# HLK-7621-ALL-KIT-V1_0.net
KiCad netlist of a schematic drawn in Altium Designer
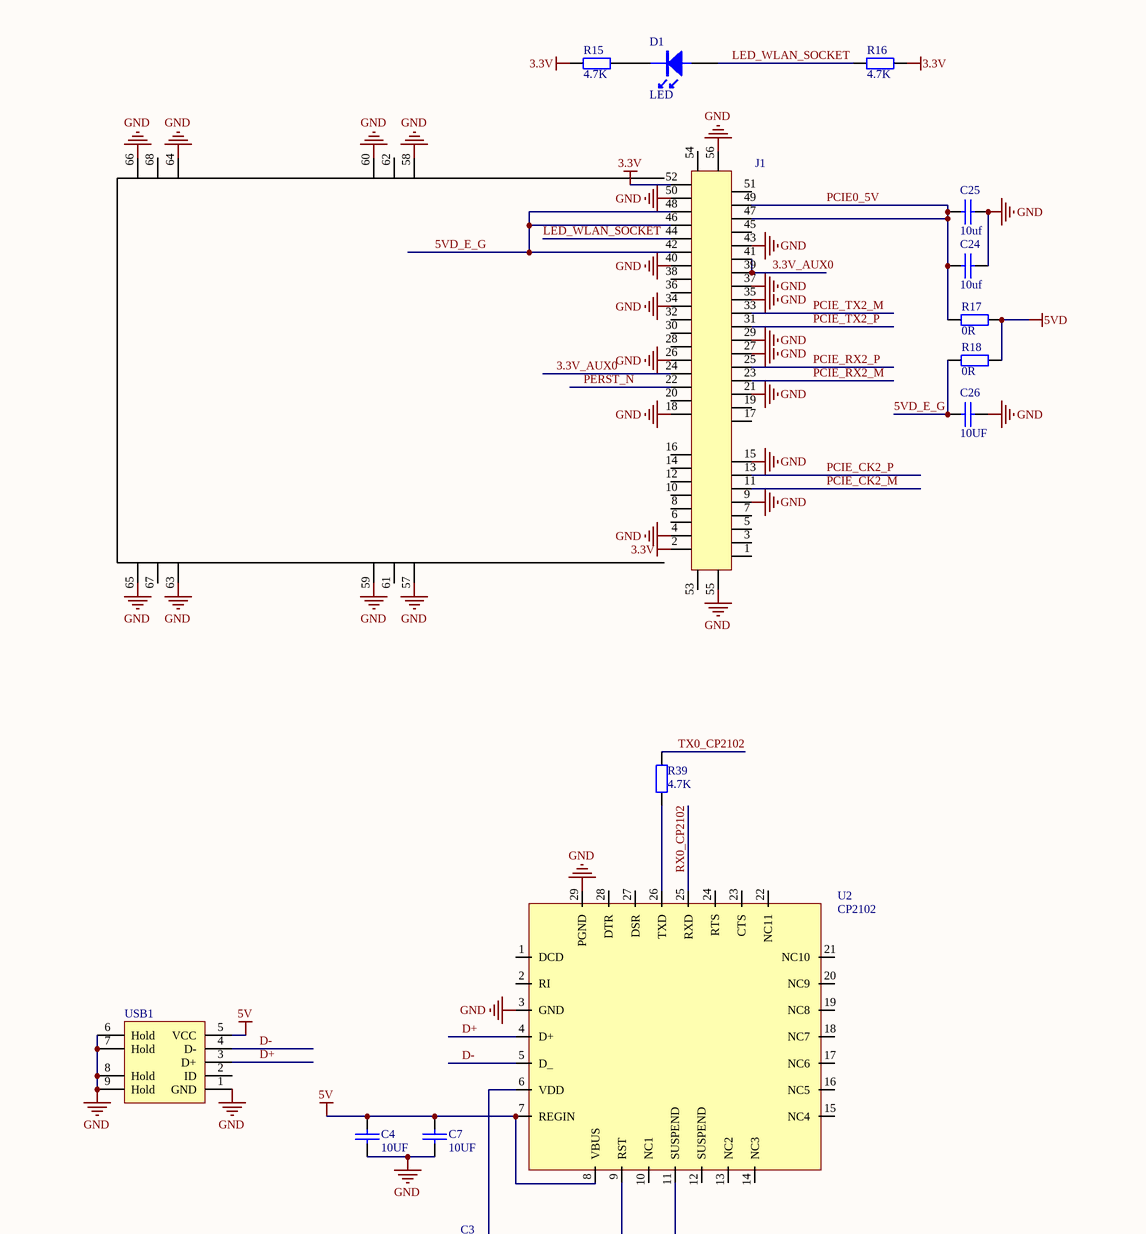
[diagram p0: HLK-7621-ALL-KIT-V1.0.SchDoc, top left]
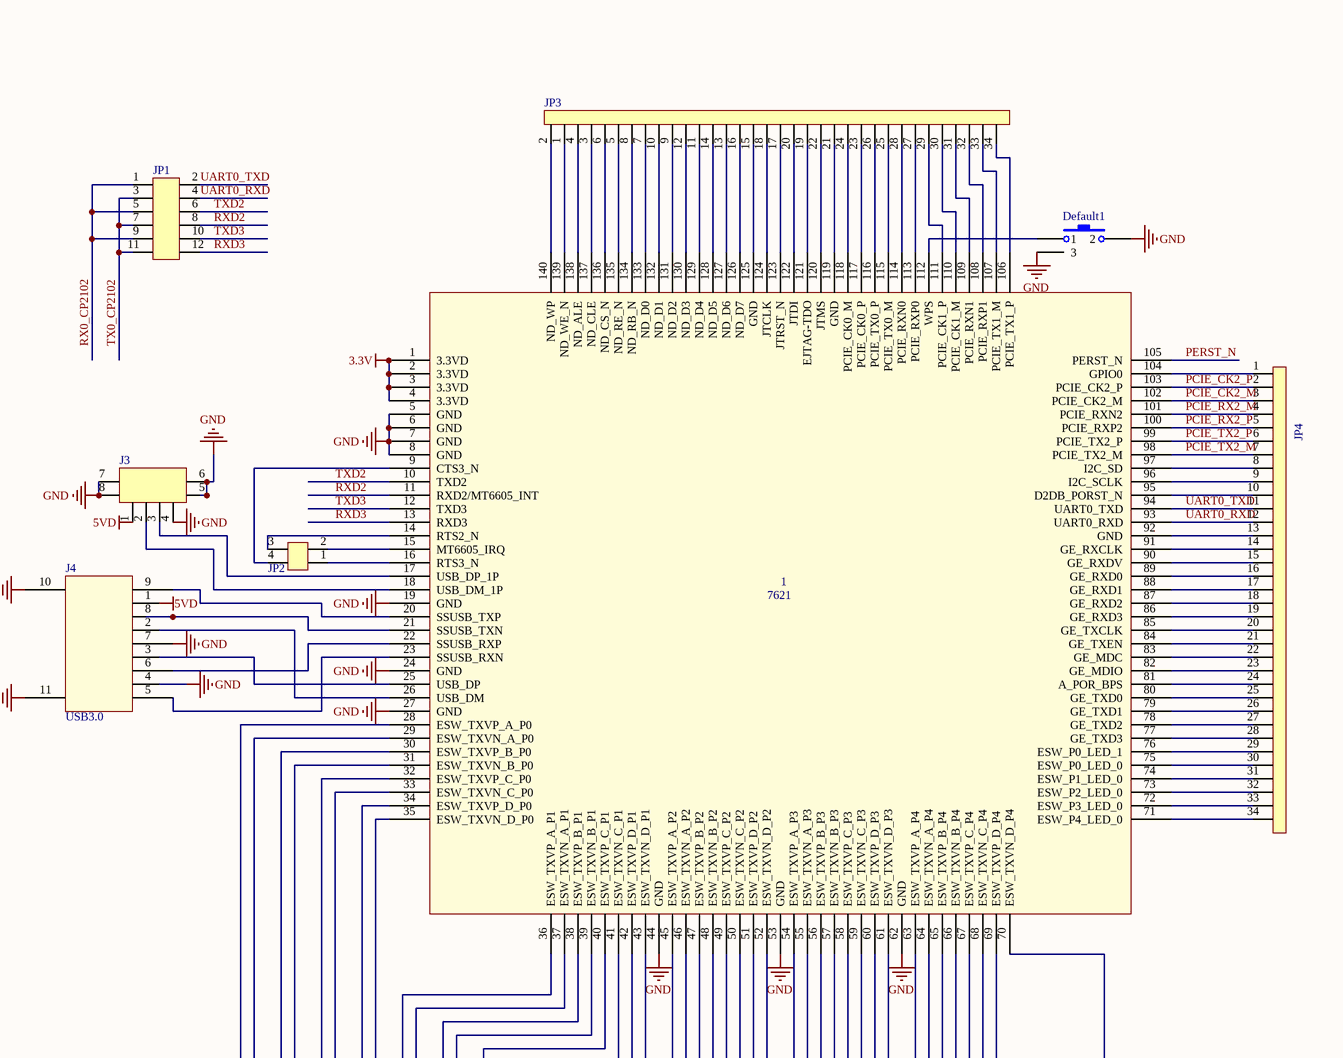
[diagram p1: HLK-7621-ALL-KIT-V1.0.SchDoc, top right]
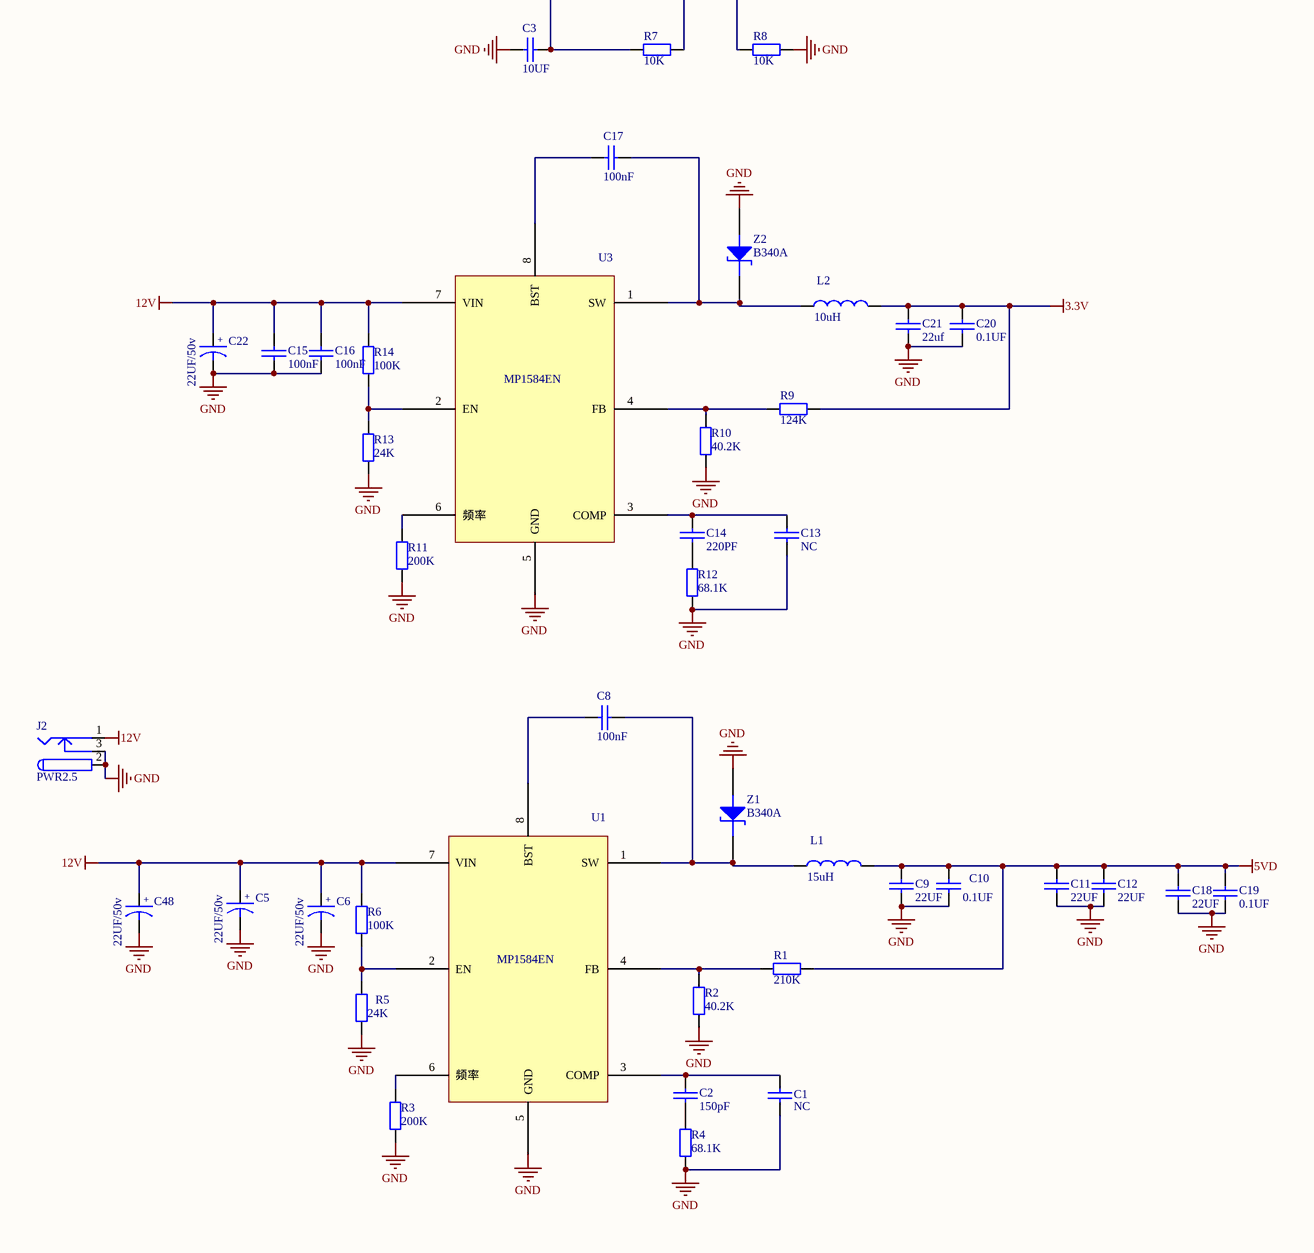
[diagram p2: HLK-7621-ALL-KIT-V1.0.SchDoc, bottom left]
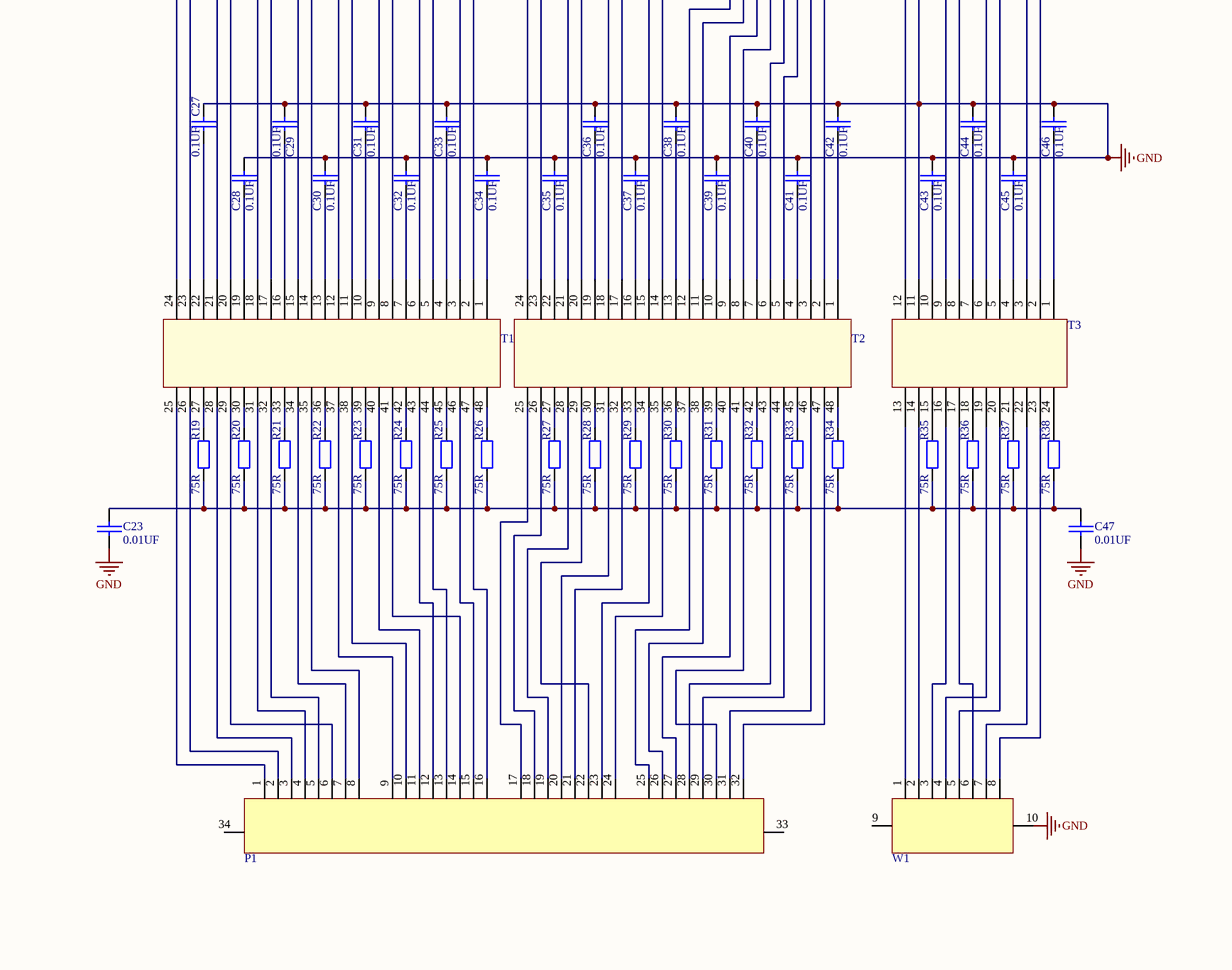
[diagram p3: HLK-7621-ALL-KIT-V1.0.SchDoc, bottom right]

(export (version "E")
  (design (tool "Eeschema 10.0.6"))
  (components
    (comp (ref "1") (value "7621") (footprint "HLK-7621") (libsource (lib "Schlib1") (part "7621")))
    (comp (ref "C1")
      (value "NC")
      (footprint "0603")
      (description "Capacitor")
      (libsource (lib "*") (part "CAP"))
    )
    (comp (ref "C2")
      (value "150pF")
      (footprint "0603")
      (description "Capacitor")
      (libsource (lib "*") (part "CAP"))
    )
    (comp (ref "C3")
      (value "10UF")
      (footprint "0603L")
      (description "Capacitor")
      (libsource (lib "*") (part "CAP"))
    )
    (comp (ref "C4")
      (value "10UF")
      (footprint "0603L")
      (description "Capacitor")
      (libsource (lib "*") (part "CAP"))
    )
    (comp (ref "C5")
      (value "22UF/50v")
      (footprint "0603")
      (description "Capacitor")
      (libsource (lib "Miscellaneous Devices") (part "CAPACITOR POL"))
    )
    (comp (ref "C6")
      (value "22UF/50v")
      (footprint "0603")
      (description "Capacitor")
      (libsource (lib "Miscellaneous Devices") (part "CAPACITOR POL"))
    )
    (comp (ref "C7")
      (value "10UF")
      (footprint "0603L")
      (description "Capacitor")
      (libsource (lib "*") (part "CAP"))
    )
    (comp (ref "C8")
      (value "100nF")
      (footprint "0603")
      (description "Capacitor")
      (libsource (lib "*") (part "CAP"))
    )
    (comp (ref "C9")
      (value "22UF")
      (footprint "0603")
      (description "Capacitor")
      (libsource (lib "*") (part "CAP"))
    )
    (comp (ref "C10")
      (value "0.1UF")
      (footprint "0603")
      (description "Capacitor")
      (libsource (lib "*") (part "CAP"))
    )
    (comp (ref "C11")
      (value "22UF")
      (footprint "0603")
      (description "Capacitor")
      (libsource (lib "*") (part "CAP"))
    )
    (comp (ref "C12")
      (value "22UF")
      (footprint "0603")
      (description "Capacitor")
      (libsource (lib "*") (part "CAP"))
    )
    (comp (ref "C13")
      (value "NC")
      (footprint "0603")
      (description "Capacitor")
      (libsource (lib "*") (part "CAP"))
    )
    (comp (ref "C14")
      (value "220PF")
      (footprint "0603")
      (description "Capacitor")
      (libsource (lib "*") (part "CAP"))
    )
    (comp (ref "C15")
      (value "100nF")
      (footprint "0603")
      (description "Capacitor")
      (libsource (lib "*") (part "CAP"))
    )
    (comp (ref "C16")
      (value "100nF")
      (footprint "0603")
      (description "Capacitor")
      (libsource (lib "*") (part "CAP"))
    )
    (comp (ref "C17")
      (value "100nF")
      (footprint "0603")
      (description "Capacitor")
      (libsource (lib "*") (part "CAP"))
    )
    (comp (ref "C18")
      (value "22UF")
      (footprint "0603")
      (description "Capacitor")
      (libsource (lib "*") (part "CAP"))
    )
    (comp (ref "C19")
      (value "0.1UF")
      (footprint "0603")
      (description "Capacitor")
      (libsource (lib "*") (part "CAP"))
    )
    (comp (ref "C20")
      (value "0.1UF")
      (footprint "0603")
      (description "Capacitor")
      (libsource (lib "*") (part "CAP"))
    )
    (comp (ref "C21")
      (value "22uf")
      (footprint "0603")
      (description "Capacitor")
      (libsource (lib "*") (part "CAP"))
    )
    (comp (ref "C22")
      (value "22UF/50v")
      (footprint "CAP_SMT_8*10.5")
      (description "Capacitor")
      (libsource (lib "Miscellaneous Devices") (part "CAPACITOR POL"))
    )
    (comp (ref "C23")
      (value "0.01UF")
      (footprint "C1206")
      (description "Capacitor")
      (libsource (lib "*") (part "CAP"))
    )
    (comp (ref "C24")
      (value "10uf")
      (footprint "C1206")
      (description "Capacitor")
      (libsource (lib "*") (part "CAP"))
    )
    (comp (ref "C25")
      (value "10uf")
      (footprint "C1206")
      (description "Capacitor")
      (libsource (lib "*") (part "CAP"))
    )
    (comp (ref "C26")
      (value "10UF")
      (footprint "C1206")
      (description "Capacitor")
      (libsource (lib "*") (part "CAP"))
    )
    (comp (ref "C27")
      (value "0.1UF")
      (footprint "C0402")
      (description "Capacitor")
      (libsource (lib "*") (part "CAP"))
    )
    (comp (ref "C28")
      (value "0.1UF")
      (footprint "C0402")
      (description "Capacitor")
      (libsource (lib "*") (part "CAP"))
    )
    (comp (ref "C29")
      (value "0.1UF")
      (footprint "C0402")
      (description "Capacitor")
      (libsource (lib "*") (part "CAP"))
    )
    (comp (ref "C30")
      (value "0.1UF")
      (footprint "C0402")
      (description "Capacitor")
      (libsource (lib "*") (part "CAP"))
    )
    (comp (ref "C31")
      (value "0.1UF")
      (footprint "C0402")
      (description "Capacitor")
      (libsource (lib "*") (part "CAP"))
    )
    (comp (ref "C32")
      (value "0.1UF")
      (footprint "C0402")
      (description "Capacitor")
      (libsource (lib "*") (part "CAP"))
    )
    (comp (ref "C33")
      (value "0.1UF")
      (footprint "C0402")
      (description "Capacitor")
      (libsource (lib "*") (part "CAP"))
    )
    (comp (ref "C34")
      (value "0.1UF")
      (footprint "C0402")
      (description "Capacitor")
      (libsource (lib "*") (part "CAP"))
    )
    (comp (ref "C35")
      (value "0.1UF")
      (footprint "C0402")
      (description "Capacitor")
      (libsource (lib "*") (part "CAP"))
    )
    (comp (ref "C36")
      (value "0.1UF")
      (footprint "C0402")
      (description "Capacitor")
      (libsource (lib "*") (part "CAP"))
    )
    (comp (ref "C37")
      (value "0.1UF")
      (footprint "C0402")
      (description "Capacitor")
      (libsource (lib "*") (part "CAP"))
    )
    (comp (ref "C38")
      (value "0.1UF")
      (footprint "C0402")
      (description "Capacitor")
      (libsource (lib "*") (part "CAP"))
    )
    (comp (ref "C39")
      (value "0.1UF")
      (footprint "C0402")
      (description "Capacitor")
      (libsource (lib "*") (part "CAP"))
    )
    (comp (ref "C40")
      (value "0.1UF")
      (footprint "C0402")
      (description "Capacitor")
      (libsource (lib "*") (part "CAP"))
    )
    (comp (ref "C41")
      (value "0.1UF")
      (footprint "C0402")
      (description "Capacitor")
      (libsource (lib "*") (part "CAP"))
    )
    (comp (ref "C42")
      (value "0.1UF")
      (footprint "C0402")
      (description "Capacitor")
      (libsource (lib "*") (part "CAP"))
    )
    (comp (ref "C43")
      (value "0.1UF")
      (footprint "C0402")
      (description "Capacitor")
      (libsource (lib "*") (part "CAP"))
    )
    (comp (ref "C44")
      (value "0.1UF")
      (footprint "C0402")
      (description "Capacitor")
      (libsource (lib "*") (part "CAP"))
    )
    (comp (ref "C45")
      (value "0.1UF")
      (footprint "C0402")
      (description "Capacitor")
      (libsource (lib "*") (part "CAP"))
    )
    (comp (ref "C46")
      (value "0.1UF")
      (footprint "C0402")
      (description "Capacitor")
      (libsource (lib "*") (part "CAP"))
    )
    (comp (ref "C47")
      (value "0.01UF")
      (footprint "C1206")
      (description "Capacitor")
      (libsource (lib "*") (part "CAP"))
    )
    (comp (ref "C48")
      (value "22UF/50v")
      (footprint "CAP_SMT_8*10.5")
      (description "Capacitor")
      (libsource (lib "Miscellaneous Devices") (part "CAPACITOR POL"))
    )
    (comp (ref "D1") (value "LED") (footprint "C1206") (libsource (lib "*") (part "LED")))
    (comp (ref "Default1")
      (value "SW-PB")
      (footprint "K5")
      (description "Switch")
      (fields (field (name "PUBLISHER") "Altium Limited"))
      (libsource (lib "Miscellaneous Devices") (part "SW-PB"))
    )
    (comp (ref "J1")
      (value "~")
      (footprint "CONSG/54/MINICARD/AS0B22-S68-7F/HALF/FUL")
      (libsource (lib "Schlib1") (part "Component_1"))
    )
    (comp (ref "J2")
      (value "PWR2.5")
      (description "Low Voltage Power Supply Connector")
      (fields (field (name "PUBLISHER") "Altium Limited"))
      (libsource (lib "*") (part "PWR2.5"))
    )
    (comp (ref "J3") (value "~") (libsource (lib "") (part "2_2")))
    (comp (ref "J4") (value "USB3.0") (libsource (lib "Schlib1") (part "USB3.0/9P/DIP/MAINSUPER")))
    (comp (ref "JP1") (value "~") (footprint "HDR2X6") (libsource (lib "") (part "Component_1_3")))
    (comp (ref "JP2") (value "~") (footprint "HDR2X2") (libsource (lib "") (part "2_1")))
    (comp (ref "JP3") (value "~") (footprint "HDR2X17") (libsource (lib "Schlib1") (part "2")))
    (comp (ref "JP4") (value "2") (footprint "HDR2X17") (libsource (lib "") (part "2_3")))
    (comp (ref "L1") (value "15uH") (footprint "CD105") (libsource (lib "startkit") (part "INDUCTOR1")))
    (comp (ref "L2") (value "10uH") (footprint "CD105") (libsource (lib "startkit") (part "INDUCTOR1")))
    (comp (ref "P1")
      (value "Component_2")
      (footprint "PHJ8X4_N")
      (libsource (lib "Schlib1") (part "Component_2"))
    )
    (comp (ref "R1")
      (value "210K")
      (footprint "0603")
      (description "Resistor")
      (fields (field (name "PUBLISHER") "Altium Limited"))
      (libsource (lib "") (part "Res2_1"))
    )
    (comp (ref "R2")
      (value "40.2K")
      (footprint "0603")
      (description "Resistor")
      (fields (field (name "PUBLISHER") "Altium Limited"))
      (libsource (lib "Miscellaneous Devices") (part "Res2"))
    )
    (comp (ref "R3")
      (value "200K")
      (footprint "0603")
      (description "Resistor")
      (fields (field (name "PUBLISHER") "Altium Limited"))
      (libsource (lib "Miscellaneous Devices") (part "Res2"))
    )
    (comp (ref "R4")
      (value "68.1K")
      (footprint "0603")
      (description "Resistor")
      (fields (field (name "PUBLISHER") "Altium Limited"))
      (libsource (lib "Miscellaneous Devices") (part "Res2"))
    )
    (comp (ref "R5")
      (value "24K")
      (footprint "0603")
      (description "Resistor")
      (fields (field (name "PUBLISHER") "Altium Limited"))
      (libsource (lib "Miscellaneous Devices") (part "Res2"))
    )
    (comp (ref "R6")
      (value "100K")
      (footprint "0603")
      (description "Resistor")
      (fields (field (name "PUBLISHER") "Altium Limited"))
      (libsource (lib "Miscellaneous Devices") (part "Res2"))
    )
    (comp (ref "R7")
      (value "10K")
      (footprint "0603L")
      (description "Resistor")
      (fields (field (name "PUBLISHER") "Altium Limited"))
      (libsource (lib "") (part "Res2_3"))
    )
    (comp (ref "R8")
      (value "10K")
      (footprint "0603L")
      (description "Resistor")
      (fields (field (name "PUBLISHER") "Altium Limited"))
      (libsource (lib "") (part "Res2_1"))
    )
    (comp (ref "R9")
      (value "124K")
      (footprint "0603")
      (description "Resistor")
      (fields (field (name "PUBLISHER") "Altium Limited"))
      (libsource (lib "") (part "Res2_1"))
    )
    (comp (ref "R10")
      (value "40.2K")
      (footprint "0603")
      (description "Resistor")
      (fields (field (name "PUBLISHER") "Altium Limited"))
      (libsource (lib "Miscellaneous Devices") (part "Res2"))
    )
    (comp (ref "R11")
      (value "200K")
      (footprint "0603")
      (description "Resistor")
      (fields (field (name "PUBLISHER") "Altium Limited"))
      (libsource (lib "Miscellaneous Devices") (part "Res2"))
    )
    (comp (ref "R12")
      (value "68.1K")
      (footprint "0603")
      (description "Resistor")
      (fields (field (name "PUBLISHER") "Altium Limited"))
      (libsource (lib "Miscellaneous Devices") (part "Res2"))
    )
    (comp (ref "R13")
      (value "24K")
      (footprint "0603")
      (description "Resistor")
      (fields (field (name "PUBLISHER") "Altium Limited"))
      (libsource (lib "Miscellaneous Devices") (part "Res2"))
    )
    (comp (ref "R14")
      (value "100K")
      (footprint "0603")
      (description "Resistor")
      (fields (field (name "PUBLISHER") "Altium Limited"))
      (libsource (lib "Miscellaneous Devices") (part "Res2"))
    )
    (comp (ref "R15")
      (value "4.7K")
      (footprint "0603")
      (description "Resistor")
      (fields (field (name "PUBLISHER") "Altium Limited"))
      (libsource (lib "") (part "Res2_1"))
    )
    (comp (ref "R16")
      (value "4.7K")
      (footprint "0603")
      (description "Resistor")
      (fields (field (name "PUBLISHER") "Altium Limited"))
      (libsource (lib "") (part "Res2_1"))
    )
    (comp (ref "R17")
      (value "0R")
      (footprint "L0805")
      (description "Resistor")
      (fields (field (name "PUBLISHER") "Altium Limited"))
      (libsource (lib "") (part "Res2_3"))
    )
    (comp (ref "R18")
      (value "0R")
      (footprint "R1206")
      (description "Resistor")
      (fields (field (name "PUBLISHER") "Altium Limited"))
      (libsource (lib "") (part "Res2_1"))
    )
    (comp (ref "R19")
      (value "75R")
      (footprint "R0402")
      (description "Resistor")
      (fields (field (name "PUBLISHER") "Altium Limited"))
      (libsource (lib "Schlib1") (part "Res2"))
    )
    (comp (ref "R20")
      (value "75R")
      (footprint "R0402")
      (description "Resistor")
      (fields (field (name "PUBLISHER") "Altium Limited"))
      (libsource (lib "Schlib1") (part "Res2"))
    )
    (comp (ref "R21")
      (value "75R")
      (footprint "R0402")
      (description "Resistor")
      (fields (field (name "PUBLISHER") "Altium Limited"))
      (libsource (lib "Schlib1") (part "Res2"))
    )
    (comp (ref "R22")
      (value "75R")
      (footprint "R0402")
      (description "Resistor")
      (fields (field (name "PUBLISHER") "Altium Limited"))
      (libsource (lib "Schlib1") (part "Res2"))
    )
    (comp (ref "R23")
      (value "75R")
      (footprint "R0402")
      (description "Resistor")
      (fields (field (name "PUBLISHER") "Altium Limited"))
      (libsource (lib "Schlib1") (part "Res2"))
    )
    (comp (ref "R24")
      (value "75R")
      (footprint "R0402")
      (description "Resistor")
      (fields (field (name "PUBLISHER") "Altium Limited"))
      (libsource (lib "Schlib1") (part "Res2"))
    )
    (comp (ref "R25")
      (value "75R")
      (footprint "R0402")
      (description "Resistor")
      (fields (field (name "PUBLISHER") "Altium Limited"))
      (libsource (lib "Schlib1") (part "Res2"))
    )
    (comp (ref "R26")
      (value "75R")
      (footprint "R0402")
      (description "Resistor")
      (fields (field (name "PUBLISHER") "Altium Limited"))
      (libsource (lib "Schlib1") (part "Res2"))
    )
    (comp (ref "R27")
      (value "75R")
      (footprint "R0402")
      (description "Resistor")
      (fields (field (name "PUBLISHER") "Altium Limited"))
      (libsource (lib "Schlib1") (part "Res2"))
    )
    (comp (ref "R28")
      (value "75R")
      (footprint "R0402")
      (description "Resistor")
      (fields (field (name "PUBLISHER") "Altium Limited"))
      (libsource (lib "Schlib1") (part "Res2"))
    )
    (comp (ref "R29")
      (value "75R")
      (footprint "R0402")
      (description "Resistor")
      (fields (field (name "PUBLISHER") "Altium Limited"))
      (libsource (lib "Schlib1") (part "Res2"))
    )
    (comp (ref "R30")
      (value "75R")
      (footprint "R0402")
      (description "Resistor")
      (fields (field (name "PUBLISHER") "Altium Limited"))
      (libsource (lib "Schlib1") (part "Res2"))
    )
    (comp (ref "R31")
      (value "75R")
      (footprint "R0402")
      (description "Resistor")
      (fields (field (name "PUBLISHER") "Altium Limited"))
      (libsource (lib "Schlib1") (part "Res2"))
    )
    (comp (ref "R32")
      (value "75R")
      (footprint "R0402")
      (description "Resistor")
      (fields (field (name "PUBLISHER") "Altium Limited"))
      (libsource (lib "Schlib1") (part "Res2"))
    )
    (comp (ref "R33")
      (value "75R")
      (footprint "R0402")
      (description "Resistor")
      (fields (field (name "PUBLISHER") "Altium Limited"))
      (libsource (lib "Schlib1") (part "Res2"))
    )
    (comp (ref "R34")
      (value "75R")
      (footprint "R0402")
      (description "Resistor")
      (fields (field (name "PUBLISHER") "Altium Limited"))
      (libsource (lib "Schlib1") (part "Res2"))
    )
    (comp (ref "R35")
      (value "75R")
      (footprint "R0402")
      (description "Resistor")
      (fields (field (name "PUBLISHER") "Altium Limited"))
      (libsource (lib "Schlib1") (part "Res2"))
    )
    (comp (ref "R36")
      (value "75R")
      (footprint "R0402")
      (description "Resistor")
      (fields (field (name "PUBLISHER") "Altium Limited"))
      (libsource (lib "Schlib1") (part "Res2"))
    )
    (comp (ref "R37")
      (value "75R")
      (footprint "R0402")
      (description "Resistor")
      (fields (field (name "PUBLISHER") "Altium Limited"))
      (libsource (lib "Schlib1") (part "Res2"))
    )
    (comp (ref "R38")
      (value "75R")
      (footprint "R0402")
      (description "Resistor")
      (fields (field (name "PUBLISHER") "Altium Limited"))
      (libsource (lib "Schlib1") (part "Res2"))
    )
    (comp (ref "R39")
      (value "4.7K")
      (footprint "0603")
      (description "Resistor")
      (fields (field (name "PUBLISHER") "Altium Limited"))
      (libsource (lib "") (part "Res2_2"))
    )
    (comp (ref "T1")
      (value "TRANSFORMER/24P/SMD/HN2429CG")
      (footprint "TRANSFORMER/48P/SMD/GS5014LF")
      (libsource (lib "Schlib1") (part "TRANSFORMER/24P/SMD/HN2429CG"))
    )
    (comp (ref "T2")
      (value "TRANSFORMER/24P/SMD/HN2429CG")
      (footprint "TRANSFORMER/48P/SMD/GS5014LF")
      (libsource (lib "Schlib1") (part "TRANSFORMER/24P/SMD/HN2429CG"))
    )
    (comp (ref "T3")
      (value "TRANSFORMER/24P/SMD/HN2429CG")
      (footprint "TRANSFORMER/24P/SMD/HN2429CG")
      (libsource (lib "") (part "TRANSFORMER/24P/SMD/HN2429CG_1"))
    )
    (comp (ref "U1") (value "MP1584EN") (footprint "SOP8_150") (libsource (lib "") (part "Component_1_2")))
    (comp (ref "U2") (value "CP2102") (footprint "cp2102") (libsource (lib "") (part "Component_1_1")))
    (comp (ref "U3") (value "MP1584EN") (footprint "SOP8_150") (libsource (lib "") (part "Component_1_2")))
    (comp (ref "USB1") (value "USB1") (footprint "usb") (libsource (lib "Schlib1") (part "USB-B")))
    (comp (ref "W1")
      (value "Component_3")
      (footprint "PCBComponent_1")
      (libsource (lib "Schlib1") (part "Component_3"))
    )
    (comp (ref "Z1")
      (value "B340A")
      (footprint "SMA")
      (description "Zener Diode")
      (libsource (lib "杂元件库") (part "ZENER2"))
    )
    (comp (ref "Z2")
      (value "B340A")
      (footprint "SMA")
      (description "Zener Diode")
      (libsource (lib "杂元件库") (part "ZENER2"))
    )
  )
  (nets
    (net (code "1") (name "/3.3V_AUX0") (class "Default")
      (node (ref "J1") (pin "24") (pinfunction "24_24") (pintype "passive"))
      (node (ref "J1") (pin "39") (pinfunction "39_39") (pintype "passive"))
      (node (ref "J1") (pin "41") (pinfunction "41_41") (pintype "passive"))
    )
    (net (code "2") (name "/5VD_E_G") (class "Default")
      (node (ref "C26") (pin "1") (pinfunction "1_1") (pintype "passive"))
      (node (ref "J1") (pin "42") (pinfunction "42_42") (pintype "passive"))
      (node (ref "J1") (pin "46") (pinfunction "46_46") (pintype "passive"))
      (node (ref "J1") (pin "48") (pinfunction "48_48") (pintype "passive"))
      (node (ref "R18") (pin "2") (pinfunction "2_2") (pintype "passive"))
    )
    (net (code "3") (name "/D+") (class "Default")
      (node (ref "U2") (pin "4") (pinfunction "D+_4") (pintype "passive"))
      (node (ref "USB1") (pin "3") (pinfunction "D+_3") (pintype "passive"))
    )
    (net (code "4") (name "/D-") (class "Default")
      (node (ref "U2") (pin "5") (pinfunction "D__5") (pintype "passive"))
      (node (ref "USB1") (pin "4") (pinfunction "D-_4") (pintype "passive"))
    )
    (net (code "5") (name "/LED_WLAN_SOCKET") (class "Default")
      (node (ref "D1") (pin "1") (pinfunction "1_1") (pintype "passive"))
      (node (ref "J1") (pin "44") (pinfunction "44_44") (pintype "passive"))
      (node (ref "R16") (pin "2") (pinfunction "2_2") (pintype "passive"))
    )
    (net (code "6") (name "/PCIE0_5V") (class "Default")
      (node (ref "C24") (pin "1") (pinfunction "1_1") (pintype "passive"))
      (node (ref "C25") (pin "1") (pinfunction "1_1") (pintype "passive"))
      (node (ref "J1") (pin "47") (pinfunction "47_47") (pintype "passive"))
      (node (ref "J1") (pin "49") (pinfunction "49_49") (pintype "passive"))
      (node (ref "R17") (pin "1") (pinfunction "1_1") (pintype "passive"))
    )
    (net (code "7") (name "/PCIE_CK2_M") (class "Default")
      (node (ref "1") (pin "102") (pinfunction "PCIE_CK2_M_102") (pintype "passive"))
      (node (ref "J1") (pin "11") (pinfunction "11_11") (pintype "passive"))
      (node (ref "JP4") (pin "3") (pinfunction "3_3") (pintype "passive"))
    )
    (net (code "8") (name "/PCIE_CK2_P") (class "Default")
      (node (ref "1") (pin "103") (pinfunction "PCIE_CK2_P_103") (pintype "passive"))
      (node (ref "J1") (pin "13") (pinfunction "13_13") (pintype "passive"))
      (node (ref "JP4") (pin "2") (pinfunction "2_2") (pintype "passive"))
    )
    (net (code "9") (name "/PCIE_RX2_M") (class "Default")
      (node (ref "1") (pin "101") (pinfunction "PCIE_RXN2_101") (pintype "passive"))
      (node (ref "J1") (pin "23") (pinfunction "23_23") (pintype "passive"))
      (node (ref "JP4") (pin "4") (pinfunction "4_4") (pintype "passive"))
    )
    (net (code "10") (name "/PCIE_RX2_P") (class "Default")
      (node (ref "1") (pin "100") (pinfunction "PCIE_RXP2_100") (pintype "passive"))
      (node (ref "J1") (pin "25") (pinfunction "25_25") (pintype "passive"))
      (node (ref "JP4") (pin "5") (pinfunction "5_5") (pintype "passive"))
    )
    (net (code "11") (name "/PCIE_TX2_M") (class "Default")
      (node (ref "1") (pin "98") (pinfunction "PCIE_TX2_M_98") (pintype "passive"))
      (node (ref "J1") (pin "33") (pinfunction "33_33") (pintype "passive"))
      (node (ref "JP4") (pin "7") (pinfunction "7_7") (pintype "passive"))
    )
    (net (code "12") (name "/PCIE_TX2_P") (class "Default")
      (node (ref "1") (pin "99") (pinfunction "PCIE_TX2_P_99") (pintype "passive"))
      (node (ref "J1") (pin "31") (pinfunction "31_31") (pintype "passive"))
      (node (ref "JP4") (pin "6") (pinfunction "6_6") (pintype "passive"))
    )
    (net (code "13") (name "/PERST_N") (class "Default")
      (node (ref "1") (pin "105") (pinfunction "PERST_N_105") (pintype "passive"))
      (node (ref "J1") (pin "22") (pinfunction "22_22") (pintype "passive"))
    )
    (net (code "14") (name "/RX0_CP2102") (class "Default")
      (node (ref "JP1") (pin "1") (pinfunction "1_1") (pintype "passive"))
      (node (ref "JP1") (pin "5") (pinfunction "5_5") (pintype "passive"))
      (node (ref "JP1") (pin "9") (pinfunction "9_9") (pintype "passive"))
      (node (ref "U2") (pin "25") (pinfunction "RXD_25") (pintype "passive"))
    )
    (net (code "15") (name "/RXD2") (class "Default")
      (node (ref "1") (pin "11") (pinfunction "RXD2/MT6605_INT_11") (pintype "passive"))
      (node (ref "JP1") (pin "8") (pinfunction "8_8") (pintype "passive"))
    )
    (net (code "16") (name "/RXD3") (class "Default")
      (node (ref "1") (pin "13") (pinfunction "RXD3_13") (pintype "passive"))
      (node (ref "JP1") (pin "12") (pinfunction "12_12") (pintype "passive"))
    )
    (net (code "17") (name "/TX0_CP2102") (class "Default")
      (node (ref "JP1") (pin "11") (pinfunction "11_11") (pintype "passive"))
      (node (ref "JP1") (pin "3") (pinfunction "3_3") (pintype "passive"))
      (node (ref "JP1") (pin "7") (pinfunction "7_7") (pintype "passive"))
      (node (ref "R39") (pin "1") (pinfunction "1_1") (pintype "passive"))
    )
    (net (code "18") (name "/TXD2") (class "Default")
      (node (ref "1") (pin "10") (pinfunction "TXD2_10") (pintype "passive"))
      (node (ref "JP1") (pin "6") (pinfunction "6_6") (pintype "passive"))
    )
    (net (code "19") (name "/TXD3") (class "Default")
      (node (ref "1") (pin "12") (pinfunction "TXD3_12") (pintype "passive"))
      (node (ref "JP1") (pin "10") (pinfunction "10_10") (pintype "passive"))
    )
    (net (code "20") (name "/UART0_RXD") (class "Default")
      (node (ref "1") (pin "93") (pinfunction "UART0_RXD_93") (pintype "passive"))
      (node (ref "JP1") (pin "4") (pinfunction "4_4") (pintype "passive"))
      (node (ref "JP4") (pin "12") (pinfunction "12_12") (pintype "passive"))
    )
    (net (code "21") (name "/UART0_TXD") (class "Default")
      (node (ref "1") (pin "94") (pinfunction "UART0_TXD_94") (pintype "passive"))
      (node (ref "JP1") (pin "2") (pinfunction "2_2") (pintype "passive"))
      (node (ref "JP4") (pin "11") (pinfunction "11_11") (pintype "passive"))
    )
    (net (code "22") (name "3.3V") (class "Default")
      (node (ref "1") (pin "1") (pinfunction "3.3VD_1") (pintype "passive"))
      (node (ref "1") (pin "2") (pinfunction "3.3VD_2") (pintype "passive"))
      (node (ref "1") (pin "3") (pinfunction "3.3VD_3") (pintype "passive"))
      (node (ref "1") (pin "4") (pinfunction "3.3VD_4") (pintype "passive"))
      (node (ref "C20") (pin "1") (pinfunction "1_1") (pintype "passive"))
      (node (ref "C21") (pin "1") (pinfunction "1_1") (pintype "passive"))
      (node (ref "J1") (pin "2") (pinfunction "2_2") (pintype "passive"))
      (node (ref "J1") (pin "52") (pinfunction "52_52") (pintype "passive"))
      (node (ref "L2") (pin "1") (pinfunction "1_1") (pintype "passive"))
      (node (ref "R15") (pin "2") (pinfunction "2_2") (pintype "passive"))
      (node (ref "R16") (pin "1") (pinfunction "1_1") (pintype "passive"))
      (node (ref "R9") (pin "1") (pinfunction "1_1") (pintype "passive"))
    )
    (net (code "23") (name "5V") (class "Default")
      (node (ref "C4") (pin "2") (pinfunction "2_2") (pintype "passive"))
      (node (ref "C7") (pin "2") (pinfunction "2_2") (pintype "passive"))
      (node (ref "U2") (pin "7") (pinfunction "REGIN_7") (pintype "passive"))
      (node (ref "U2") (pin "8") (pinfunction "VBUS_8") (pintype "passive"))
      (node (ref "USB1") (pin "5") (pinfunction "VCC_5") (pintype "passive"))
    )
    (net (code "24") (name "5VD") (class "Default")
      (node (ref "C10") (pin "1") (pinfunction "1_1") (pintype "passive"))
      (node (ref "C11") (pin "1") (pinfunction "1_1") (pintype "passive"))
      (node (ref "C12") (pin "1") (pinfunction "1_1") (pintype "passive"))
      (node (ref "C18") (pin "1") (pinfunction "1_1") (pintype "passive"))
      (node (ref "C19") (pin "1") (pinfunction "1_1") (pintype "passive"))
      (node (ref "C9") (pin "1") (pinfunction "1_1") (pintype "passive"))
      (node (ref "J3") (pin "1") (pinfunction "1_1") (pintype "passive"))
      (node (ref "J4") (pin "1") (pinfunction "1_1") (pintype "passive"))
      (node (ref "L1") (pin "1") (pinfunction "1_1") (pintype "passive"))
      (node (ref "R1") (pin "1") (pinfunction "1_1") (pintype "passive"))
      (node (ref "R17") (pin "2") (pinfunction "2_2") (pintype "passive"))
      (node (ref "R18") (pin "1") (pinfunction "1_1") (pintype "passive"))
    )
    (net (code "25") (name "12V") (class "Default")
      (node (ref "C15") (pin "1") (pinfunction "1_1") (pintype "passive"))
      (node (ref "C16") (pin "1") (pinfunction "1_1") (pintype "passive"))
      (node (ref "C22") (pin "1") (pinfunction "1_1") (pintype "passive"))
      (node (ref "C48") (pin "1") (pinfunction "1_1") (pintype "passive"))
      (node (ref "C5") (pin "1") (pinfunction "1_1") (pintype "passive"))
      (node (ref "C6") (pin "1") (pinfunction "1_1") (pintype "passive"))
      (node (ref "J2") (pin "1") (pinfunction "1_1") (pintype "power_in"))
      (node (ref "R14") (pin "2") (pinfunction "2_2") (pintype "passive"))
      (node (ref "R6") (pin "2") (pinfunction "2_2") (pintype "passive"))
      (node (ref "U1") (pin "7") (pinfunction "VIN_7") (pintype "passive"))
      (node (ref "U3") (pin "7") (pinfunction "VIN_7") (pintype "passive"))
    )
    (net (code "26") (name "GND") (class "Default")
      (node (ref "1") (pin "19") (pinfunction "GND_19") (pintype "passive"))
      (node (ref "1") (pin "24") (pinfunction "GND_24") (pintype "passive"))
      (node (ref "1") (pin "27") (pinfunction "GND_27") (pintype "passive"))
      (node (ref "1") (pin "44") (pinfunction "GND_44") (pintype "passive"))
      (node (ref "1") (pin "5") (pinfunction "GND_5") (pintype "passive"))
      (node (ref "1") (pin "53") (pinfunction "GND_53") (pintype "passive"))
      (node (ref "1") (pin "6") (pinfunction "GND_6") (pintype "passive"))
      (node (ref "1") (pin "62") (pinfunction "GND_62") (pintype "passive"))
      (node (ref "1") (pin "64") (pinfunction "ESW_TXVN_A_P4_64") (pintype "passive"))
      (node (ref "1") (pin "7") (pinfunction "GND_7") (pintype "passive"))
      (node (ref "1") (pin "8") (pinfunction "GND_8") (pintype "passive"))
      (node (ref "C1") (pin "2") (pinfunction "2_2") (pintype "passive"))
      (node (ref "C10") (pin "2") (pinfunction "2_2") (pintype "passive"))
      (node (ref "C11") (pin "2") (pinfunction "2_2") (pintype "passive"))
      (node (ref "C12") (pin "2") (pinfunction "2_2") (pintype "passive"))
      (node (ref "C13") (pin "2") (pinfunction "2_2") (pintype "passive"))
      (node (ref "C15") (pin "2") (pinfunction "2_2") (pintype "passive"))
      (node (ref "C16") (pin "2") (pinfunction "2_2") (pintype "passive"))
      (node (ref "C18") (pin "2") (pinfunction "2_2") (pintype "passive"))
      (node (ref "C19") (pin "2") (pinfunction "2_2") (pintype "passive"))
      (node (ref "C20") (pin "2") (pinfunction "2_2") (pintype "passive"))
      (node (ref "C21") (pin "2") (pinfunction "2_2") (pintype "passive"))
      (node (ref "C22") (pin "2") (pinfunction "2_2") (pintype "passive"))
      (node (ref "C23") (pin "2") (pinfunction "2_2") (pintype "passive"))
      (node (ref "C24") (pin "2") (pinfunction "2_2") (pintype "passive"))
      (node (ref "C25") (pin "2") (pinfunction "2_2") (pintype "passive"))
      (node (ref "C26") (pin "2") (pinfunction "2_2") (pintype "passive"))
      (node (ref "C27") (pin "1") (pinfunction "1_1") (pintype "passive"))
      (node (ref "C28") (pin "1") (pinfunction "1_1") (pintype "passive"))
      (node (ref "C29") (pin "1") (pinfunction "1_1") (pintype "passive"))
      (node (ref "C3") (pin "1") (pinfunction "1_1") (pintype "passive"))
      (node (ref "C30") (pin "1") (pinfunction "1_1") (pintype "passive"))
      (node (ref "C31") (pin "1") (pinfunction "1_1") (pintype "passive"))
      (node (ref "C32") (pin "1") (pinfunction "1_1") (pintype "passive"))
      (node (ref "C33") (pin "1") (pinfunction "1_1") (pintype "passive"))
      (node (ref "C34") (pin "1") (pinfunction "1_1") (pintype "passive"))
      (node (ref "C35") (pin "1") (pinfunction "1_1") (pintype "passive"))
      (node (ref "C36") (pin "1") (pinfunction "1_1") (pintype "passive"))
      (node (ref "C37") (pin "1") (pinfunction "1_1") (pintype "passive"))
      (node (ref "C38") (pin "1") (pinfunction "1_1") (pintype "passive"))
      (node (ref "C39") (pin "1") (pinfunction "1_1") (pintype "passive"))
      (node (ref "C4") (pin "1") (pinfunction "1_1") (pintype "passive"))
      (node (ref "C40") (pin "1") (pinfunction "1_1") (pintype "passive"))
      (node (ref "C41") (pin "1") (pinfunction "1_1") (pintype "passive"))
      (node (ref "C42") (pin "1") (pinfunction "1_1") (pintype "passive"))
      (node (ref "C43") (pin "1") (pinfunction "1_1") (pintype "passive"))
      (node (ref "C44") (pin "1") (pinfunction "1_1") (pintype "passive"))
      (node (ref "C45") (pin "1") (pinfunction "1_1") (pintype "passive"))
      (node (ref "C46") (pin "1") (pinfunction "1_1") (pintype "passive"))
      (node (ref "C47") (pin "2") (pinfunction "2_2") (pintype "passive"))
      (node (ref "C48") (pin "2") (pinfunction "2_2") (pintype "passive"))
      (node (ref "C5") (pin "2") (pinfunction "2_2") (pintype "passive"))
      (node (ref "C6") (pin "2") (pinfunction "2_2") (pintype "passive"))
      (node (ref "C7") (pin "1") (pinfunction "1_1") (pintype "passive"))
      (node (ref "C9") (pin "2") (pinfunction "2_2") (pintype "passive"))
      (node (ref "Default1") (pin "2") (pinfunction "2_2") (pintype "passive"))
      (node (ref "Default1") (pin "3") (pinfunction "3_3") (pintype "passive"))
      (node (ref "J1") (pin "15") (pinfunction "15_15") (pintype "passive"))
      (node (ref "J1") (pin "18") (pinfunction "18_18") (pintype "passive"))
      (node (ref "J1") (pin "21") (pinfunction "21_21") (pintype "passive"))
      (node (ref "J1") (pin "26") (pinfunction "26_26") (pintype "passive"))
      (node (ref "J1") (pin "27") (pinfunction "27_27") (pintype "passive"))
      (node (ref "J1") (pin "29") (pinfunction "29_29") (pintype "passive"))
      (node (ref "J1") (pin "34") (pinfunction "34_34") (pintype "passive"))
      (node (ref "J1") (pin "35") (pinfunction "35_35") (pintype "passive"))
      (node (ref "J1") (pin "37") (pinfunction "37_37") (pintype "passive"))
      (node (ref "J1") (pin "4") (pinfunction "4_4") (pintype "passive"))
      (node (ref "J1") (pin "40") (pinfunction "40_40") (pintype "passive"))
      (node (ref "J1") (pin "43") (pinfunction "43_43") (pintype "passive"))
      (node (ref "J1") (pin "50") (pinfunction "50_50") (pintype "passive"))
      (node (ref "J1") (pin "55") (pinfunction "53_55") (pintype "passive"))
      (node (ref "J1") (pin "56") (pinfunction "54_56") (pintype "passive"))
      (node (ref "J1") (pin "57") (pinfunction "57_57") (pintype "passive"))
      (node (ref "J1") (pin "58") (pinfunction "58_58") (pintype "passive"))
      (node (ref "J1") (pin "59") (pinfunction "59_59") (pintype "passive"))
      (node (ref "J1") (pin "60") (pinfunction "60_60") (pintype "passive"))
      (node (ref "J1") (pin "63") (pinfunction "63_63") (pintype "passive"))
      (node (ref "J1") (pin "64") (pinfunction "64_64") (pintype "passive"))
      (node (ref "J1") (pin "65") (pinfunction "65_65") (pintype "passive"))
      (node (ref "J1") (pin "66") (pinfunction "66_66") (pintype "passive"))
      (node (ref "J1") (pin "9") (pinfunction "9_9") (pintype "passive"))
      (node (ref "J2") (pin "2") (pinfunction "2_2") (pintype "power_in"))
      (node (ref "J2") (pin "3") (pinfunction "3_3") (pintype "power_in"))
      (node (ref "J3") (pin "4") (pinfunction "4_4") (pintype "passive"))
      (node (ref "J3") (pin "5") (pinfunction "5_5") (pintype "passive"))
      (node (ref "J3") (pin "6") (pinfunction "6_6") (pintype "passive"))
      (node (ref "J3") (pin "7") (pinfunction "7_7") (pintype "passive"))
      (node (ref "J3") (pin "8") (pinfunction "8_8") (pintype "passive"))
      (node (ref "J4") (pin "10") (pinfunction "10_10") (pintype "passive"))
      (node (ref "J4") (pin "11") (pinfunction "11_11") (pintype "passive"))
      (node (ref "J4") (pin "4") (pinfunction "4_4") (pintype "passive"))
      (node (ref "J4") (pin "7") (pinfunction "7_7") (pintype "passive"))
      (node (ref "R10") (pin "1") (pinfunction "1_1") (pintype "passive"))
      (node (ref "R11") (pin "1") (pinfunction "1_1") (pintype "passive"))
      (node (ref "R12") (pin "1") (pinfunction "1_1") (pintype "passive"))
      (node (ref "R13") (pin "1") (pinfunction "1_1") (pintype "passive"))
      (node (ref "R2") (pin "1") (pinfunction "1_1") (pintype "passive"))
      (node (ref "R3") (pin "1") (pinfunction "1_1") (pintype "passive"))
      (node (ref "R4") (pin "1") (pinfunction "1_1") (pintype "passive"))
      (node (ref "R5") (pin "1") (pinfunction "1_1") (pintype "passive"))
      (node (ref "R8") (pin "1") (pinfunction "1_1") (pintype "passive"))
      (node (ref "T3") (pin "11") (pinfunction "11_11") (pintype "passive"))
      (node (ref "U1") (pin "5") (pinfunction "GND_5") (pintype "passive"))
      (node (ref "U2") (pin "29") (pinfunction "PGND_29") (pintype "passive"))
      (node (ref "U2") (pin "3") (pinfunction "GND_3") (pintype "passive"))
      (node (ref "U3") (pin "5") (pinfunction "GND_5") (pintype "passive"))
      (node (ref "USB1") (pin "1") (pinfunction "GND_1") (pintype "passive"))
      (node (ref "USB1") (pin "6") (pinfunction "Hold_6") (pintype "passive"))
      (node (ref "USB1") (pin "7") (pinfunction "Hold_7") (pintype "passive"))
      (node (ref "USB1") (pin "8") (pinfunction "Hold_8") (pintype "passive"))
      (node (ref "USB1") (pin "9") (pinfunction "Hold_9") (pintype "passive"))
      (node (ref "W1") (pin "10") (pinfunction "10_10") (pintype "passive"))
      (node (ref "Z1") (pin "1") (pinfunction "A_1") (pintype "passive"))
      (node (ref "Z2") (pin "1") (pinfunction "A_1") (pintype "passive"))
    )
    (net (code "27") (name "Net-(1-A_POR_BPS)") (class "Default")
      (node (ref "1") (pin "81") (pinfunction "A_POR_BPS_81") (pintype "passive"))
      (node (ref "JP4") (pin "24") (pinfunction "24_24") (pintype "passive"))
    )
    (net (code "28") (name "Net-(1-CTS3_N)") (class "Default")
      (node (ref "1") (pin "9") (pinfunction "CTS3_N_9") (pintype "passive"))
      (node (ref "JP2") (pin "4") (pinfunction "4_4") (pintype "passive"))
    )
    (net (code "29") (name "Net-(1-D2DB_PORST_N)") (class "Default")
      (node (ref "1") (pin "95") (pinfunction "D2DB_PORST_N_95") (pintype "passive"))
      (node (ref "JP4") (pin "10") (pinfunction "10_10") (pintype "passive"))
    )
    (net (code "30") (name "Net-(1-EJTAG-TDO)") (class "Default")
      (node (ref "1") (pin "121") (pinfunction "EJTAG-TDO_121") (pintype "passive"))
      (node (ref "JP3") (pin "19") (pinfunction "19_19") (pintype "passive"))
    )
    (net (code "31") (name "Net-(1-ESW_P0_LED_0)") (class "Default")
      (node (ref "1") (pin "75") (pinfunction "ESW_P0_LED_0_75") (pintype "passive"))
      (node (ref "JP4") (pin "30") (pinfunction "30_30") (pintype "passive"))
    )
    (net (code "32") (name "Net-(1-ESW_P0_LED_1)") (class "Default")
      (node (ref "1") (pin "76") (pinfunction "ESW_P0_LED_1_76") (pintype "passive"))
      (node (ref "JP4") (pin "29") (pinfunction "29_29") (pintype "passive"))
    )
    (net (code "33") (name "Net-(1-ESW_P1_LED_0)") (class "Default")
      (node (ref "1") (pin "74") (pinfunction "ESW_P1_LED_0_74") (pintype "passive"))
      (node (ref "JP4") (pin "31") (pinfunction "31_31") (pintype "passive"))
    )
    (net (code "34") (name "Net-(1-ESW_P2_LED_0)") (class "Default")
      (node (ref "1") (pin "73") (pinfunction "ESW_P2_LED_0_73") (pintype "passive"))
      (node (ref "JP4") (pin "32") (pinfunction "32_32") (pintype "passive"))
    )
    (net (code "35") (name "Net-(1-ESW_P3_LED_0)") (class "Default")
      (node (ref "1") (pin "72") (pinfunction "ESW_P3_LED_0_72") (pintype "passive"))
      (node (ref "JP4") (pin "33") (pinfunction "33_33") (pintype "passive"))
    )
    (net (code "36") (name "Net-(1-ESW_P4_LED_0)") (class "Default")
      (node (ref "1") (pin "71") (pinfunction "ESW_P4_LED_0_71") (pintype "passive"))
      (node (ref "JP4") (pin "34") (pinfunction "34_34") (pintype "passive"))
    )
    (net (code "37") (name "Net-(1-ESW_TXVN_A_P0)") (class "Default")
      (node (ref "1") (pin "29") (pinfunction "ESW_TXVN_A_P0_29") (pintype "passive"))
      (node (ref "T1") (pin "23") (pinfunction "23_23") (pintype "passive"))
    )
    (net (code "38") (name "Net-(1-ESW_TXVN_A_P1)") (class "Default")
      (node (ref "1") (pin "37") (pinfunction "ESW_TXVN_A_P1_37") (pintype "passive"))
      (node (ref "T1") (pin "11") (pinfunction "11_11") (pintype "passive"))
    )
    (net (code "39") (name "Net-(1-ESW_TXVN_A_P2)") (class "Default")
      (node (ref "1") (pin "46") (pinfunction "ESW_TXVN_A_P2_46") (pintype "passive"))
      (node (ref "T2") (pin "23") (pinfunction "23_23") (pintype "passive"))
    )
    (net (code "40") (name "Net-(1-ESW_TXVN_A_P3)") (class "Default")
      (node (ref "1") (pin "55") (pinfunction "ESW_TXVN_A_P3_55") (pintype "passive"))
      (node (ref "T2") (pin "11") (pinfunction "11_11") (pintype "passive"))
    )
    (net (code "41") (name "Net-(1-ESW_TXVN_B_P0)") (class "Default")
      (node (ref "1") (pin "31") (pinfunction "ESW_TXVN_B_P0_31") (pintype "passive"))
      (node (ref "T1") (pin "20") (pinfunction "20_20") (pintype "passive"))
    )
    (net (code "42") (name "Net-(1-ESW_TXVN_B_P1)") (class "Default")
      (node (ref "1") (pin "39") (pinfunction "ESW_TXVN_B_P1_39") (pintype "passive"))
      (node (ref "T1") (pin "8") (pinfunction "8_8") (pintype "passive"))
    )
    (net (code "43") (name "Net-(1-ESW_TXVN_B_P2)") (class "Default")
      (node (ref "1") (pin "48") (pinfunction "ESW_TXVN_B_P2_48") (pintype "passive"))
      (node (ref "T2") (pin "20") (pinfunction "20_20") (pintype "passive"))
    )
    (net (code "44") (name "Net-(1-ESW_TXVN_B_P3)") (class "Default")
      (node (ref "1") (pin "57") (pinfunction "ESW_TXVN_B_P3_57") (pintype "passive"))
      (node (ref "T2") (pin "8") (pinfunction "8_8") (pintype "passive"))
    )
    (net (code "45") (name "Net-(1-ESW_TXVN_B_P4)") (class "Default")
      (node (ref "1") (pin "66") (pinfunction "ESW_TXVN_B_P4_66") (pintype "passive"))
      (node (ref "T3") (pin "8") (pinfunction "8_8") (pintype "passive"))
    )
    (net (code "46") (name "Net-(1-ESW_TXVN_C_P0)") (class "Default")
      (node (ref "1") (pin "33") (pinfunction "ESW_TXVN_C_P0_33") (pintype "passive"))
      (node (ref "T1") (pin "17") (pinfunction "17_17") (pintype "passive"))
    )
    (net (code "47") (name "Net-(1-ESW_TXVN_C_P1)") (class "Default")
      (node (ref "1") (pin "41") (pinfunction "ESW_TXVN_C_P1_41") (pintype "passive"))
      (node (ref "T1") (pin "5") (pinfunction "5_5") (pintype "passive"))
    )
    (net (code "48") (name "Net-(1-ESW_TXVN_C_P2)") (class "Default")
      (node (ref "1") (pin "50") (pinfunction "ESW_TXVN_C_P2_50") (pintype "passive"))
      (node (ref "T2") (pin "17") (pinfunction "17_17") (pintype "passive"))
    )
    (net (code "49") (name "Net-(1-ESW_TXVN_C_P3)") (class "Default")
      (node (ref "1") (pin "59") (pinfunction "ESW_TXVN_C_P3_59") (pintype "passive"))
      (node (ref "T2") (pin "5") (pinfunction "5_5") (pintype "passive"))
    )
    (net (code "50") (name "Net-(1-ESW_TXVN_C_P4)") (class "Default")
      (node (ref "1") (pin "68") (pinfunction "ESW_TXVN_C_P4_68") (pintype "passive"))
      (node (ref "T3") (pin "5") (pinfunction "5_5") (pintype "passive"))
    )
    (net (code "51") (name "Net-(1-ESW_TXVN_D_P0)") (class "Default")
      (node (ref "1") (pin "35") (pinfunction "ESW_TXVN_D_P0_35") (pintype "passive"))
      (node (ref "T1") (pin "14") (pinfunction "14_14") (pintype "passive"))
    )
    (net (code "52") (name "Net-(1-ESW_TXVN_D_P1)") (class "Default")
      (node (ref "1") (pin "43") (pinfunction "ESW_TXVN_D_P1_43") (pintype "passive"))
      (node (ref "T1") (pin "2") (pinfunction "2_2") (pintype "passive"))
    )
    (net (code "53") (name "Net-(1-ESW_TXVN_D_P2)") (class "Default")
      (node (ref "1") (pin "52") (pinfunction "ESW_TXVN_D_P2_52") (pintype "passive"))
      (node (ref "T2") (pin "14") (pinfunction "14_14") (pintype "passive"))
    )
    (net (code "54") (name "Net-(1-ESW_TXVN_D_P3)") (class "Default")
      (node (ref "1") (pin "61") (pinfunction "ESW_TXVN_D_P3_61") (pintype "passive"))
      (node (ref "T2") (pin "2") (pinfunction "2_2") (pintype "passive"))
    )
    (net (code "55") (name "Net-(1-ESW_TXVN_D_P4)") (class "Default")
      (node (ref "1") (pin "70") (pinfunction "ESW_TXVN_D_P4_70") (pintype "passive"))
      (node (ref "T3") (pin "2") (pinfunction "2_2") (pintype "passive"))
    )
    (net (code "56") (name "Net-(1-ESW_TXVP_A_P0)") (class "Default")
      (node (ref "1") (pin "28") (pinfunction "ESW_TXVP_A_P0_28") (pintype "passive"))
      (node (ref "T1") (pin "24") (pinfunction "24_24") (pintype "passive"))
    )
    (net (code "57") (name "Net-(1-ESW_TXVP_A_P1)") (class "Default")
      (node (ref "1") (pin "36") (pinfunction "ESW_TXVP_A_P1_36") (pintype "passive"))
      (node (ref "T1") (pin "12") (pinfunction "12_12") (pintype "passive"))
    )
    (net (code "58") (name "Net-(1-ESW_TXVP_A_P2)") (class "Default")
      (node (ref "1") (pin "45") (pinfunction "ESW_TXVP_A_P2_45") (pintype "passive"))
      (node (ref "T2") (pin "24") (pinfunction "24_24") (pintype "passive"))
    )
    (net (code "59") (name "Net-(1-ESW_TXVP_A_P3)") (class "Default")
      (node (ref "1") (pin "54") (pinfunction "ESW_TXVP_A_P3_54") (pintype "passive"))
      (node (ref "T2") (pin "12") (pinfunction "12_12") (pintype "passive"))
    )
    (net (code "60") (name "Net-(1-ESW_TXVP_A_P4)") (class "Default")
      (node (ref "1") (pin "63") (pinfunction "ESW_TXVP_A_P4_63") (pintype "passive"))
      (node (ref "T3") (pin "12") (pinfunction "12_12") (pintype "passive"))
    )
    (net (code "61") (name "Net-(1-ESW_TXVP_B_P0)") (class "Default")
      (node (ref "1") (pin "30") (pinfunction "ESW_TXVP_B_P0_30") (pintype "passive"))
      (node (ref "T1") (pin "21") (pinfunction "21_21") (pintype "passive"))
    )
    (net (code "62") (name "Net-(1-ESW_TXVP_B_P1)") (class "Default")
      (node (ref "1") (pin "38") (pinfunction "ESW_TXVP_B_P1_38") (pintype "passive"))
      (node (ref "T1") (pin "9") (pinfunction "9_9") (pintype "passive"))
    )
    (net (code "63") (name "Net-(1-ESW_TXVP_B_P2)") (class "Default")
      (node (ref "1") (pin "47") (pinfunction "ESW_TXVP_B_P2_47") (pintype "passive"))
      (node (ref "T2") (pin "21") (pinfunction "21_21") (pintype "passive"))
    )
    (net (code "64") (name "Net-(1-ESW_TXVP_B_P3)") (class "Default")
      (node (ref "1") (pin "56") (pinfunction "ESW_TXVP_B_P3_56") (pintype "passive"))
      (node (ref "T2") (pin "9") (pinfunction "9_9") (pintype "passive"))
    )
    (net (code "65") (name "Net-(1-ESW_TXVP_B_P4)") (class "Default")
      (node (ref "1") (pin "65") (pinfunction "ESW_TXVP_B_P4_65") (pintype "passive"))
      (node (ref "T3") (pin "9") (pinfunction "9_9") (pintype "passive"))
    )
    (net (code "66") (name "Net-(1-ESW_TXVP_C_P0)") (class "Default")
      (node (ref "1") (pin "32") (pinfunction "ESW_TXVP_C_P0_32") (pintype "passive"))
      (node (ref "T1") (pin "18") (pinfunction "18_18") (pintype "passive"))
    )
    (net (code "67") (name "Net-(1-ESW_TXVP_C_P1)") (class "Default")
      (node (ref "1") (pin "40") (pinfunction "ESW_TXVP_C_P1_40") (pintype "passive"))
      (node (ref "T1") (pin "6") (pinfunction "6_6") (pintype "passive"))
    )
    (net (code "68") (name "Net-(1-ESW_TXVP_C_P2)") (class "Default")
      (node (ref "1") (pin "49") (pinfunction "ESW_TXVP_C_P2_49") (pintype "passive"))
      (node (ref "T2") (pin "18") (pinfunction "18_18") (pintype "passive"))
    )
    (net (code "69") (name "Net-(1-ESW_TXVP_C_P3)") (class "Default")
      (node (ref "1") (pin "58") (pinfunction "ESW_TXVP_C_P3_58") (pintype "passive"))
      (node (ref "T2") (pin "6") (pinfunction "6_6") (pintype "passive"))
    )
    (net (code "70") (name "Net-(1-ESW_TXVP_C_P4)") (class "Default")
      (node (ref "1") (pin "67") (pinfunction "ESW_TXVP_C_P4_67") (pintype "passive"))
      (node (ref "T3") (pin "6") (pinfunction "6_6") (pintype "passive"))
    )
    (net (code "71") (name "Net-(1-ESW_TXVP_D_P0)") (class "Default")
      (node (ref "1") (pin "34") (pinfunction "ESW_TXVP_D_P0_34") (pintype "passive"))
      (node (ref "T1") (pin "15") (pinfunction "15_15") (pintype "passive"))
    )
    (net (code "72") (name "Net-(1-ESW_TXVP_D_P1)") (class "Default")
      (node (ref "1") (pin "42") (pinfunction "ESW_TXVP_D_P1_42") (pintype "passive"))
      (node (ref "T1") (pin "3") (pinfunction "3_3") (pintype "passive"))
    )
    (net (code "73") (name "Net-(1-ESW_TXVP_D_P2)") (class "Default")
      (node (ref "1") (pin "51") (pinfunction "ESW_TXVP_D_P2_51") (pintype "passive"))
      (node (ref "T2") (pin "15") (pinfunction "15_15") (pintype "passive"))
    )
    (net (code "74") (name "Net-(1-ESW_TXVP_D_P3)") (class "Default")
      (node (ref "1") (pin "60") (pinfunction "ESW_TXVP_D_P3_60") (pintype "passive"))
      (node (ref "T2") (pin "3") (pinfunction "3_3") (pintype "passive"))
    )
    (net (code "75") (name "Net-(1-ESW_TXVP_D_P4)") (class "Default")
      (node (ref "1") (pin "69") (pinfunction "ESW_TXVP_D_P4_69") (pintype "passive"))
      (node (ref "T3") (pin "3") (pinfunction "3_3") (pintype "passive"))
    )
    (net (code "76") (name "Net-(1-GE_MDC)") (class "Default")
      (node (ref "1") (pin "83") (pinfunction "GE_MDC_83") (pintype "passive"))
      (node (ref "JP4") (pin "22") (pinfunction "22_22") (pintype "passive"))
    )
    (net (code "77") (name "Net-(1-GE_MDIO)") (class "Default")
      (node (ref "1") (pin "82") (pinfunction "GE_MDIO_82") (pintype "passive"))
      (node (ref "JP4") (pin "23") (pinfunction "23_23") (pintype "passive"))
    )
    (net (code "78") (name "Net-(1-GE_RXCLK)") (class "Default")
      (node (ref "1") (pin "91") (pinfunction "GE_RXCLK_91") (pintype "passive"))
      (node (ref "JP4") (pin "14") (pinfunction "14_14") (pintype "passive"))
    )
    (net (code "79") (name "Net-(1-GE_RXD0)") (class "Default")
      (node (ref "1") (pin "89") (pinfunction "GE_RXD0_89") (pintype "passive"))
      (node (ref "JP4") (pin "16") (pinfunction "16_16") (pintype "passive"))
    )
    (net (code "80") (name "Net-(1-GE_RXD1)") (class "Default")
      (node (ref "1") (pin "88") (pinfunction "GE_RXD1_88") (pintype "passive"))
      (node (ref "JP4") (pin "17") (pinfunction "17_17") (pintype "passive"))
    )
    (net (code "81") (name "Net-(1-GE_RXD2)") (class "Default")
      (node (ref "1") (pin "87") (pinfunction "GE_RXD2_87") (pintype "passive"))
      (node (ref "JP4") (pin "18") (pinfunction "18_18") (pintype "passive"))
    )
    (net (code "82") (name "Net-(1-GE_RXD3)") (class "Default")
      (node (ref "1") (pin "86") (pinfunction "GE_RXD3_86") (pintype "passive"))
      (node (ref "JP4") (pin "19") (pinfunction "19_19") (pintype "passive"))
    )
    (net (code "83") (name "Net-(1-GE_RXDV)") (class "Default")
      (node (ref "1") (pin "90") (pinfunction "GE_RXDV_90") (pintype "passive"))
      (node (ref "JP4") (pin "15") (pinfunction "15_15") (pintype "passive"))
    )
    (net (code "84") (name "Net-(1-GE_TXCLK)") (class "Default")
      (node (ref "1") (pin "85") (pinfunction "GE_TXCLK_85") (pintype "passive"))
      (node (ref "JP4") (pin "20") (pinfunction "20_20") (pintype "passive"))
    )
    (net (code "85") (name "Net-(1-GE_TXD0)") (class "Default")
      (node (ref "1") (pin "80") (pinfunction "GE_TXD0_80") (pintype "passive"))
      (node (ref "JP4") (pin "25") (pinfunction "25_25") (pintype "passive"))
    )
    (net (code "86") (name "Net-(1-GE_TXD1)") (class "Default")
      (node (ref "1") (pin "79") (pinfunction "GE_TXD1_79") (pintype "passive"))
      (node (ref "JP4") (pin "26") (pinfunction "26_26") (pintype "passive"))
    )
    (net (code "87") (name "Net-(1-GE_TXD2)") (class "Default")
      (node (ref "1") (pin "78") (pinfunction "GE_TXD2_78") (pintype "passive"))
      (node (ref "JP4") (pin "27") (pinfunction "27_27") (pintype "passive"))
    )
    (net (code "88") (name "Net-(1-GE_TXD3)") (class "Default")
      (node (ref "1") (pin "77") (pinfunction "GE_TXD3_77") (pintype "passive"))
      (node (ref "JP4") (pin "28") (pinfunction "28_28") (pintype "passive"))
    )
    (net (code "89") (name "Net-(1-GE_TXEN)") (class "Default")
      (node (ref "1") (pin "84") (pinfunction "GE_TXEN_84") (pintype "passive"))
      (node (ref "JP4") (pin "21") (pinfunction "21_21") (pintype "passive"))
    )
    (net (code "90") (name "Net-(1-GND-Pad92)") (class "Default")
      (node (ref "1") (pin "92") (pinfunction "GND_92") (pintype "passive"))
      (node (ref "JP4") (pin "13") (pinfunction "13_13") (pintype "passive"))
    )
    (net (code "91") (name "Net-(1-GND-Pad119)") (class "Default")
      (node (ref "1") (pin "119") (pinfunction "GND_119") (pintype "passive"))
      (node (ref "JP3") (pin "21") (pinfunction "21_21") (pintype "passive"))
    )
    (net (code "92") (name "Net-(1-GND-Pad125)") (class "Default")
      (node (ref "1") (pin "125") (pinfunction "GND_125") (pintype "passive"))
      (node (ref "JP3") (pin "15") (pinfunction "15_15") (pintype "passive"))
    )
    (net (code "93") (name "Net-(1-GPIO0)") (class "Default")
      (node (ref "1") (pin "104") (pinfunction "GPIO0_104") (pintype "passive"))
      (node (ref "JP4") (pin "1") (pinfunction "1_1") (pintype "passive"))
    )
    (net (code "94") (name "Net-(1-I2C_SCLK)") (class "Default")
      (node (ref "1") (pin "96") (pinfunction "I2C_SCLK_96") (pintype "passive"))
      (node (ref "JP4") (pin "9") (pinfunction "9_9") (pintype "passive"))
    )
    (net (code "95") (name "Net-(1-I2C_SD)") (class "Default")
      (node (ref "1") (pin "97") (pinfunction "I2C_SD_97") (pintype "passive"))
      (node (ref "JP4") (pin "8") (pinfunction "8_8") (pintype "passive"))
    )
    (net (code "96") (name "Net-(1-JTCLK)") (class "Default")
      (node (ref "1") (pin "124") (pinfunction "JTCLK_124") (pintype "passive"))
      (node (ref "JP3") (pin "18") (pinfunction "18_18") (pintype "passive"))
    )
    (net (code "97") (name "Net-(1-JTDI)") (class "Default")
      (node (ref "1") (pin "122") (pinfunction "JTDI_122") (pintype "passive"))
      (node (ref "JP3") (pin "20") (pinfunction "20_20") (pintype "passive"))
    )
    (net (code "98") (name "Net-(1-JTMS)") (class "Default")
      (node (ref "1") (pin "120") (pinfunction "JTMS_120") (pintype "passive"))
      (node (ref "JP3") (pin "22") (pinfunction "22_22") (pintype "passive"))
    )
    (net (code "99") (name "Net-(1-JTRST_N)") (class "Default")
      (node (ref "1") (pin "123") (pinfunction "JTRST_N_123") (pintype "passive"))
      (node (ref "JP3") (pin "17") (pinfunction "17_17") (pintype "passive"))
    )
    (net (code "100") (name "Net-(1-MT6605_IRQ)") (class "Default")
      (node (ref "1") (pin "15") (pinfunction "MT6605_IRQ_15") (pintype "passive"))
      (node (ref "JP2") (pin "2") (pinfunction "2_2") (pintype "passive"))
    )
    (net (code "101") (name "Net-(1-ND_ALE)") (class "Default")
      (node (ref "1") (pin "138") (pinfunction "ND_ALE_138") (pintype "passive"))
      (node (ref "JP3") (pin "4") (pinfunction "4_4") (pintype "passive"))
    )
    (net (code "102") (name "Net-(1-ND_CLE)") (class "Default")
      (node (ref "1") (pin "137") (pinfunction "ND_CLE_137") (pintype "passive"))
      (node (ref "JP3") (pin "3") (pinfunction "3_3") (pintype "passive"))
    )
    (net (code "103") (name "Net-(1-ND_CS_N)") (class "Default")
      (node (ref "1") (pin "136") (pinfunction "ND_CS_N_136") (pintype "passive"))
      (node (ref "JP3") (pin "6") (pinfunction "6_6") (pintype "passive"))
    )
    (net (code "104") (name "Net-(1-ND_D0)") (class "Default")
      (node (ref "1") (pin "133") (pinfunction "ND_D0_133") (pintype "passive"))
      (node (ref "JP3") (pin "7") (pinfunction "7_7") (pintype "passive"))
    )
    (net (code "105") (name "Net-(1-ND_D1)") (class "Default")
      (node (ref "1") (pin "132") (pinfunction "ND_D1_132") (pintype "passive"))
      (node (ref "JP3") (pin "10") (pinfunction "10_10") (pintype "passive"))
    )
    (net (code "106") (name "Net-(1-ND_D2)") (class "Default")
      (node (ref "1") (pin "131") (pinfunction "ND_D2_131") (pintype "passive"))
      (node (ref "JP3") (pin "9") (pinfunction "9_9") (pintype "passive"))
    )
    (net (code "107") (name "Net-(1-ND_D3)") (class "Default")
      (node (ref "1") (pin "130") (pinfunction "ND_D3_130") (pintype "passive"))
      (node (ref "JP3") (pin "12") (pinfunction "12_12") (pintype "passive"))
    )
    (net (code "108") (name "Net-(1-ND_D4)") (class "Default")
      (node (ref "1") (pin "129") (pinfunction "ND_D4_129") (pintype "passive"))
      (node (ref "JP3") (pin "11") (pinfunction "11_11") (pintype "passive"))
    )
    (net (code "109") (name "Net-(1-ND_D5)") (class "Default")
      (node (ref "1") (pin "128") (pinfunction "ND_D5_128") (pintype "passive"))
      (node (ref "JP3") (pin "14") (pinfunction "14_14") (pintype "passive"))
    )
    (net (code "110") (name "Net-(1-ND_D6)") (class "Default")
      (node (ref "1") (pin "127") (pinfunction "ND_D6_127") (pintype "passive"))
      (node (ref "JP3") (pin "13") (pinfunction "13_13") (pintype "passive"))
    )
    (net (code "111") (name "Net-(1-ND_D7)") (class "Default")
      (node (ref "1") (pin "126") (pinfunction "ND_D7_126") (pintype "passive"))
      (node (ref "JP3") (pin "16") (pinfunction "16_16") (pintype "passive"))
    )
    (net (code "112") (name "Net-(1-ND_RB_N)") (class "Default")
      (node (ref "1") (pin "134") (pinfunction "ND_RB_N_134") (pintype "passive"))
      (node (ref "JP3") (pin "8") (pinfunction "8_8") (pintype "passive"))
    )
    (net (code "113") (name "Net-(1-ND_RE_N)") (class "Default")
      (node (ref "1") (pin "135") (pinfunction "ND_RE_N_135") (pintype "passive"))
      (node (ref "JP3") (pin "5") (pinfunction "5_5") (pintype "passive"))
    )
    (net (code "114") (name "Net-(1-ND_WE_N)") (class "Default")
      (node (ref "1") (pin "139") (pinfunction "ND_WE_N_139") (pintype "passive"))
      (node (ref "JP3") (pin "1") (pinfunction "1_1") (pintype "passive"))
    )
    (net (code "115") (name "Net-(1-ND_WP)") (class "Default")
      (node (ref "1") (pin "140") (pinfunction "ND_WP_140") (pintype "passive"))
      (node (ref "JP3") (pin "2") (pinfunction "2_2") (pintype "passive"))
    )
    (net (code "116") (name "Net-(1-PCIE_CK0_M)") (class "Default")
      (node (ref "1") (pin "118") (pinfunction "PCIE_CK0_M_118") (pintype "passive"))
      (node (ref "JP3") (pin "24") (pinfunction "24_24") (pintype "passive"))
    )
    (net (code "117") (name "Net-(1-PCIE_CK0_P)") (class "Default")
      (node (ref "1") (pin "117") (pinfunction "PCIE_CK0_P_117") (pintype "passive"))
      (node (ref "JP3") (pin "23") (pinfunction "23_23") (pintype "passive"))
    )
    (net (code "118") (name "Net-(1-PCIE_CK1_M)") (class "Default")
      (node (ref "1") (pin "110") (pinfunction "PCIE_CK1_M_110") (pintype "passive"))
      (node (ref "JP3") (pin "30") (pinfunction "30_30") (pintype "passive"))
    )
    (net (code "119") (name "Net-(1-PCIE_CK1_P)") (class "Default")
      (node (ref "1") (pin "111") (pinfunction "PCIE_CK1_P_111") (pintype "passive"))
      (node (ref "JP3") (pin "29") (pinfunction "29_29") (pintype "passive"))
    )
    (net (code "120") (name "Net-(1-PCIE_RXN0)") (class "Default")
      (node (ref "1") (pin "114") (pinfunction "PCIE_RXN0_114") (pintype "passive"))
      (node (ref "JP3") (pin "28") (pinfunction "28_28") (pintype "passive"))
    )
    (net (code "121") (name "Net-(1-PCIE_RXN1)") (class "Default")
      (node (ref "1") (pin "109") (pinfunction "PCIE_RXN1_109") (pintype "passive"))
      (node (ref "JP3") (pin "31") (pinfunction "31_31") (pintype "passive"))
    )
    (net (code "122") (name "Net-(1-PCIE_RXP0)") (class "Default")
      (node (ref "1") (pin "113") (pinfunction "PCIE_RXP0_113") (pintype "passive"))
      (node (ref "JP3") (pin "27") (pinfunction "27_27") (pintype "passive"))
    )
    (net (code "123") (name "Net-(1-PCIE_RXP1)") (class "Default")
      (node (ref "1") (pin "108") (pinfunction "PCIE_RXP1_108") (pintype "passive"))
      (node (ref "JP3") (pin "32") (pinfunction "32_32") (pintype "passive"))
    )
    (net (code "124") (name "Net-(1-PCIE_TX0_M)") (class "Default")
      (node (ref "1") (pin "115") (pinfunction "PCIE_TX0_M_115") (pintype "passive"))
      (node (ref "JP3") (pin "25") (pinfunction "25_25") (pintype "passive"))
    )
    (net (code "125") (name "Net-(1-PCIE_TX0_P)") (class "Default")
      (node (ref "1") (pin "116") (pinfunction "PCIE_TX0_P_116") (pintype "passive"))
      (node (ref "JP3") (pin "26") (pinfunction "26_26") (pintype "passive"))
    )
    (net (code "126") (name "Net-(1-PCIE_TX1_M)") (class "Default")
      (node (ref "1") (pin "107") (pinfunction "PCIE_TX1_M_107") (pintype "passive"))
      (node (ref "JP3") (pin "33") (pinfunction "33_33") (pintype "passive"))
    )
    (net (code "127") (name "Net-(1-PCIE_TX1_P)") (class "Default")
      (node (ref "1") (pin "106") (pinfunction "PCIE_TX1_P_106") (pintype "passive"))
      (node (ref "JP3") (pin "34") (pinfunction "34_34") (pintype "passive"))
    )
    (net (code "128") (name "Net-(1-RTS2_N)") (class "Default")
      (node (ref "1") (pin "14") (pinfunction "RTS2_N_14") (pintype "passive"))
      (node (ref "JP2") (pin "3") (pinfunction "3_3") (pintype "passive"))
    )
    (net (code "129") (name "Net-(1-RTS3_N)") (class "Default")
      (node (ref "1") (pin "16") (pinfunction "RTS3_N_16") (pintype "passive"))
      (node (ref "JP2") (pin "1") (pinfunction "1_1") (pintype "passive"))
    )
    (net (code "130") (name "Net-(1-SSUSB_RXN)") (class "Default")
      (node (ref "1") (pin "23") (pinfunction "SSUSB_RXN_23") (pintype "passive"))
      (node (ref "J4") (pin "5") (pinfunction "5_5") (pintype "passive"))
    )
    (net (code "131") (name "Net-(1-SSUSB_RXP)") (class "Default")
      (node (ref "1") (pin "22") (pinfunction "SSUSB_RXP_22") (pintype "passive"))
      (node (ref "J4") (pin "6") (pinfunction "6_6") (pintype "passive"))
    )
    (net (code "132") (name "Net-(1-SSUSB_TXN)") (class "Default")
      (node (ref "1") (pin "21") (pinfunction "SSUSB_TXN_21") (pintype "passive"))
      (node (ref "J4") (pin "8") (pinfunction "8_8") (pintype "passive"))
    )
    (net (code "133") (name "Net-(1-SSUSB_TXP)") (class "Default")
      (node (ref "1") (pin "20") (pinfunction "SSUSB_TXP_20") (pintype "passive"))
      (node (ref "J4") (pin "9") (pinfunction "9_9") (pintype "passive"))
    )
    (net (code "134") (name "Net-(1-USB_DM)") (class "Default")
      (node (ref "1") (pin "26") (pinfunction "USB_DM_26") (pintype "passive"))
      (node (ref "J4") (pin "2") (pinfunction "2_2") (pintype "passive"))
    )
    (net (code "135") (name "Net-(1-USB_DM_1P)") (class "Default")
      (node (ref "1") (pin "18") (pinfunction "USB_DM_1P_18") (pintype "passive"))
      (node (ref "J3") (pin "2") (pinfunction "2_2") (pintype "passive"))
    )
    (net (code "136") (name "Net-(1-USB_DP)") (class "Default")
      (node (ref "1") (pin "25") (pinfunction "USB_DP_25") (pintype "passive"))
      (node (ref "J4") (pin "3") (pinfunction "3_3") (pintype "passive"))
    )
    (net (code "137") (name "Net-(1-USB_DP_1P)") (class "Default")
      (node (ref "1") (pin "17") (pinfunction "USB_DP_1P_17") (pintype "passive"))
      (node (ref "J3") (pin "3") (pinfunction "3_3") (pintype "passive"))
    )
    (net (code "138") (name "Net-(1-WPS)") (class "Default")
      (node (ref "1") (pin "112") (pinfunction "WPS_112") (pintype "passive"))
      (node (ref "Default1") (pin "1") (pinfunction "1_1") (pintype "passive"))
    )
    (net (code "139") (name "Net-(C2-Pad2)") (class "Default")
      (node (ref "C2") (pin "2") (pinfunction "2_2") (pintype "passive"))
      (node (ref "R4") (pin "2") (pinfunction "2_2") (pintype "passive"))
    )
    (net (code "140") (name "Net-(C14-Pad2)") (class "Default")
      (node (ref "C14") (pin "2") (pinfunction "2_2") (pintype "passive"))
      (node (ref "R12") (pin "2") (pinfunction "2_2") (pintype "passive"))
    )
    (net (code "141") (name "Net-(C23-Pad1)") (class "Default")
      (node (ref "C23") (pin "1") (pinfunction "1_1") (pintype "passive"))
      (node (ref "C47") (pin "1") (pinfunction "1_1") (pintype "passive"))
      (node (ref "R19") (pin "1") (pinfunction "1_1") (pintype "passive"))
      (node (ref "R20") (pin "1") (pinfunction "1_1") (pintype "passive"))
      (node (ref "R21") (pin "1") (pinfunction "1_1") (pintype "passive"))
      (node (ref "R22") (pin "1") (pinfunction "1_1") (pintype "passive"))
      (node (ref "R23") (pin "1") (pinfunction "1_1") (pintype "passive"))
      (node (ref "R24") (pin "1") (pinfunction "1_1") (pintype "passive"))
      (node (ref "R25") (pin "1") (pinfunction "1_1") (pintype "passive"))
      (node (ref "R26") (pin "1") (pinfunction "1_1") (pintype "passive"))
      (node (ref "R27") (pin "1") (pinfunction "1_1") (pintype "passive"))
      (node (ref "R28") (pin "1") (pinfunction "1_1") (pintype "passive"))
      (node (ref "R29") (pin "1") (pinfunction "1_1") (pintype "passive"))
      (node (ref "R30") (pin "1") (pinfunction "1_1") (pintype "passive"))
      (node (ref "R31") (pin "1") (pinfunction "1_1") (pintype "passive"))
      (node (ref "R32") (pin "1") (pinfunction "1_1") (pintype "passive"))
      (node (ref "R33") (pin "1") (pinfunction "1_1") (pintype "passive"))
      (node (ref "R34") (pin "1") (pinfunction "1_1") (pintype "passive"))
      (node (ref "R35") (pin "1") (pinfunction "1_1") (pintype "passive"))
      (node (ref "R36") (pin "1") (pinfunction "1_1") (pintype "passive"))
      (node (ref "R37") (pin "1") (pinfunction "1_1") (pintype "passive"))
      (node (ref "R38") (pin "1") (pinfunction "1_1") (pintype "passive"))
    )
    (net (code "142") (name "Net-(C27-Pad2)") (class "Default")
      (node (ref "C27") (pin "2") (pinfunction "2_2") (pintype "passive"))
      (node (ref "T1") (pin "22") (pinfunction "22_22") (pintype "passive"))
    )
    (net (code "143") (name "Net-(C28-Pad2)") (class "Default")
      (node (ref "C28") (pin "2") (pinfunction "2_2") (pintype "passive"))
      (node (ref "T1") (pin "19") (pinfunction "19_19") (pintype "passive"))
    )
    (net (code "144") (name "Net-(C29-Pad2)") (class "Default")
      (node (ref "C29") (pin "2") (pinfunction "2_2") (pintype "passive"))
      (node (ref "T1") (pin "16") (pinfunction "16_16") (pintype "passive"))
    )
    (net (code "145") (name "Net-(C30-Pad2)") (class "Default")
      (node (ref "C30") (pin "2") (pinfunction "2_2") (pintype "passive"))
      (node (ref "T1") (pin "13") (pinfunction "13_13") (pintype "passive"))
    )
    (net (code "146") (name "Net-(C31-Pad2)") (class "Default")
      (node (ref "C31") (pin "2") (pinfunction "2_2") (pintype "passive"))
      (node (ref "T1") (pin "10") (pinfunction "10_10") (pintype "passive"))
    )
    (net (code "147") (name "Net-(C32-Pad2)") (class "Default")
      (node (ref "C32") (pin "2") (pinfunction "2_2") (pintype "passive"))
      (node (ref "T1") (pin "7") (pinfunction "7_7") (pintype "passive"))
    )
    (net (code "148") (name "Net-(C33-Pad2)") (class "Default")
      (node (ref "C33") (pin "2") (pinfunction "2_2") (pintype "passive"))
      (node (ref "T1") (pin "4") (pinfunction "4_4") (pintype "passive"))
    )
    (net (code "149") (name "Net-(C34-Pad2)") (class "Default")
      (node (ref "C34") (pin "2") (pinfunction "2_2") (pintype "passive"))
      (node (ref "T1") (pin "1") (pinfunction "1_1") (pintype "passive"))
    )
    (net (code "150") (name "Net-(C35-Pad2)") (class "Default")
      (node (ref "C35") (pin "2") (pinfunction "2_2") (pintype "passive"))
      (node (ref "T2") (pin "22") (pinfunction "22_22") (pintype "passive"))
    )
    (net (code "151") (name "Net-(C36-Pad2)") (class "Default")
      (node (ref "C36") (pin "2") (pinfunction "2_2") (pintype "passive"))
      (node (ref "T2") (pin "19") (pinfunction "19_19") (pintype "passive"))
    )
    (net (code "152") (name "Net-(C37-Pad2)") (class "Default")
      (node (ref "C37") (pin "2") (pinfunction "2_2") (pintype "passive"))
      (node (ref "T2") (pin "16") (pinfunction "16_16") (pintype "passive"))
    )
    (net (code "153") (name "Net-(C38-Pad2)") (class "Default")
      (node (ref "C38") (pin "2") (pinfunction "2_2") (pintype "passive"))
      (node (ref "T2") (pin "13") (pinfunction "13_13") (pintype "passive"))
    )
    (net (code "154") (name "Net-(C39-Pad2)") (class "Default")
      (node (ref "C39") (pin "2") (pinfunction "2_2") (pintype "passive"))
      (node (ref "T2") (pin "10") (pinfunction "10_10") (pintype "passive"))
    )
    (net (code "155") (name "Net-(C40-Pad2)") (class "Default")
      (node (ref "C40") (pin "2") (pinfunction "2_2") (pintype "passive"))
      (node (ref "T2") (pin "7") (pinfunction "7_7") (pintype "passive"))
    )
    (net (code "156") (name "Net-(C41-Pad2)") (class "Default")
      (node (ref "C41") (pin "2") (pinfunction "2_2") (pintype "passive"))
      (node (ref "T2") (pin "4") (pinfunction "4_4") (pintype "passive"))
    )
    (net (code "157") (name "Net-(C42-Pad2)") (class "Default")
      (node (ref "C42") (pin "2") (pinfunction "2_2") (pintype "passive"))
      (node (ref "T2") (pin "1") (pinfunction "1_1") (pintype "passive"))
    )
    (net (code "158") (name "Net-(C43-Pad2)") (class "Default")
      (node (ref "C43") (pin "2") (pinfunction "2_2") (pintype "passive"))
      (node (ref "T3") (pin "10") (pinfunction "10_10") (pintype "passive"))
    )
    (net (code "159") (name "Net-(C44-Pad2)") (class "Default")
      (node (ref "C44") (pin "2") (pinfunction "2_2") (pintype "passive"))
      (node (ref "T3") (pin "7") (pinfunction "7_7") (pintype "passive"))
    )
    (net (code "160") (name "Net-(C45-Pad2)") (class "Default")
      (node (ref "C45") (pin "2") (pinfunction "2_2") (pintype "passive"))
      (node (ref "T3") (pin "4") (pinfunction "4_4") (pintype "passive"))
    )
    (net (code "161") (name "Net-(C46-Pad2)") (class "Default")
      (node (ref "C46") (pin "2") (pinfunction "2_2") (pintype "passive"))
      (node (ref "T3") (pin "1") (pinfunction "1_1") (pintype "passive"))
    )
    (net (code "162") (name "Net-(D1-Pad2)") (class "Default")
      (node (ref "D1") (pin "2") (pinfunction "2_2") (pintype "passive"))
      (node (ref "R15") (pin "1") (pinfunction "1_1") (pintype "passive"))
    )
    (net (code "163") (name "Net-(P1-Pad1)") (class "Default")
      (node (ref "P1") (pin "1") (pinfunction "1_1") (pintype "passive"))
      (node (ref "T1") (pin "25") (pinfunction "25_25") (pintype "passive"))
    )
    (net (code "164") (name "Net-(P1-Pad2)") (class "Default")
      (node (ref "P1") (pin "2") (pinfunction "2_2") (pintype "passive"))
      (node (ref "T1") (pin "26") (pinfunction "26_26") (pintype "passive"))
    )
    (net (code "165") (name "Net-(P1-Pad3)") (class "Default")
      (node (ref "P1") (pin "3") (pinfunction "3_3") (pintype "passive"))
      (node (ref "T1") (pin "28") (pinfunction "28_28") (pintype "passive"))
    )
    (net (code "166") (name "Net-(P1-Pad4)") (class "Default")
      (node (ref "P1") (pin "4") (pinfunction "4_4") (pintype "passive"))
      (node (ref "T1") (pin "31") (pinfunction "31_31") (pintype "passive"))
    )
    (net (code "167") (name "Net-(P1-Pad5)") (class "Default")
      (node (ref "P1") (pin "5") (pinfunction "5_5") (pintype "passive"))
      (node (ref "T1") (pin "32") (pinfunction "32_32") (pintype "passive"))
    )
    (net (code "168") (name "Net-(P1-Pad6)") (class "Default")
      (node (ref "P1") (pin "6") (pinfunction "6_6") (pintype "passive"))
      (node (ref "T1") (pin "29") (pinfunction "29_29") (pintype "passive"))
    )
    (net (code "169") (name "Net-(P1-Pad7)") (class "Default")
      (node (ref "P1") (pin "7") (pinfunction "7_7") (pintype "passive"))
      (node (ref "T1") (pin "34") (pinfunction "34_34") (pintype "passive"))
    )
    (net (code "170") (name "Net-(P1-Pad8)") (class "Default")
      (node (ref "P1") (pin "8") (pinfunction "8_8") (pintype "passive"))
      (node (ref "T1") (pin "35") (pinfunction "35_35") (pintype "passive"))
    )
    (net (code "171") (name "Net-(P1-Pad9)") (class "Default")
      (node (ref "P1") (pin "9") (pinfunction "9_9") (pintype "passive"))
      (node (ref "T1") (pin "37") (pinfunction "37_37") (pintype "passive"))
    )
    (net (code "172") (name "Net-(P1-Pad10)") (class "Default")
      (node (ref "P1") (pin "10") (pinfunction "10_10") (pintype "passive"))
      (node (ref "T1") (pin "38") (pinfunction "38_38") (pintype "passive"))
    )
    (net (code "173") (name "Net-(P1-Pad11)") (class "Default")
      (node (ref "P1") (pin "11") (pinfunction "11_11") (pintype "passive"))
      (node (ref "T1") (pin "40") (pinfunction "40_40") (pintype "passive"))
    )
    (net (code "174") (name "Net-(P1-Pad12)") (class "Default")
      (node (ref "P1") (pin "12") (pinfunction "12_12") (pintype "passive"))
      (node (ref "T1") (pin "43") (pinfunction "43_43") (pintype "passive"))
    )
    (net (code "175") (name "Net-(P1-Pad13)") (class "Default")
      (node (ref "P1") (pin "13") (pinfunction "13_13") (pintype "passive"))
      (node (ref "T1") (pin "44") (pinfunction "44_44") (pintype "passive"))
    )
    (net (code "176") (name "Net-(P1-Pad14)") (class "Default")
      (node (ref "P1") (pin "14") (pinfunction "14_14") (pintype "passive"))
      (node (ref "T1") (pin "41") (pinfunction "41_41") (pintype "passive"))
    )
    (net (code "177") (name "Net-(P1-Pad15)") (class "Default")
      (node (ref "P1") (pin "15") (pinfunction "15_15") (pintype "passive"))
      (node (ref "T1") (pin "46") (pinfunction "46_46") (pintype "passive"))
    )
    (net (code "178") (name "Net-(P1-Pad16)") (class "Default")
      (node (ref "P1") (pin "16") (pinfunction "16_16") (pintype "passive"))
      (node (ref "T1") (pin "47") (pinfunction "47_47") (pintype "passive"))
    )
    (net (code "179") (name "Net-(P1-Pad17)") (class "Default")
      (node (ref "P1") (pin "17") (pinfunction "17_17") (pintype "passive"))
      (node (ref "T2") (pin "25") (pinfunction "25_25") (pintype "passive"))
    )
    (net (code "180") (name "Net-(P1-Pad18)") (class "Default")
      (node (ref "P1") (pin "18") (pinfunction "18_18") (pintype "passive"))
      (node (ref "T2") (pin "26") (pinfunction "26_26") (pintype "passive"))
    )
    (net (code "181") (name "Net-(P1-Pad19)") (class "Default")
      (node (ref "P1") (pin "19") (pinfunction "19_19") (pintype "passive"))
      (node (ref "T2") (pin "28") (pinfunction "28_28") (pintype "passive"))
    )
    (net (code "182") (name "Net-(P1-Pad20)") (class "Default")
      (node (ref "P1") (pin "20") (pinfunction "20_20") (pintype "passive"))
      (node (ref "T2") (pin "31") (pinfunction "31_31") (pintype "passive"))
    )
    (net (code "183") (name "Net-(P1-Pad21)") (class "Default")
      (node (ref "P1") (pin "21") (pinfunction "21_21") (pintype "passive"))
      (node (ref "T2") (pin "32") (pinfunction "32_32") (pintype "passive"))
    )
    (net (code "184") (name "Net-(P1-Pad22)") (class "Default")
      (node (ref "P1") (pin "22") (pinfunction "22_22") (pintype "passive"))
      (node (ref "T2") (pin "29") (pinfunction "29_29") (pintype "passive"))
    )
    (net (code "185") (name "Net-(P1-Pad23)") (class "Default")
      (node (ref "P1") (pin "23") (pinfunction "23_23") (pintype "passive"))
      (node (ref "T2") (pin "34") (pinfunction "34_34") (pintype "passive"))
    )
    (net (code "186") (name "Net-(P1-Pad24)") (class "Default")
      (node (ref "P1") (pin "24") (pinfunction "24_24") (pintype "passive"))
      (node (ref "T2") (pin "35") (pinfunction "35_35") (pintype "passive"))
    )
    (net (code "187") (name "Net-(P1-Pad25)") (class "Default")
      (node (ref "P1") (pin "25") (pinfunction "25_25") (pintype "passive"))
      (node (ref "T2") (pin "37") (pinfunction "37_37") (pintype "passive"))
    )
    (net (code "188") (name "Net-(P1-Pad26)") (class "Default")
      (node (ref "P1") (pin "26") (pinfunction "26_26") (pintype "passive"))
      (node (ref "T2") (pin "38") (pinfunction "38_38") (pintype "passive"))
    )
    (net (code "189") (name "Net-(P1-Pad27)") (class "Default")
      (node (ref "P1") (pin "27") (pinfunction "27_27") (pintype "passive"))
      (node (ref "T2") (pin "40") (pinfunction "40_40") (pintype "passive"))
    )
    (net (code "190") (name "Net-(P1-Pad28)") (class "Default")
      (node (ref "P1") (pin "28") (pinfunction "28_28") (pintype "passive"))
      (node (ref "T2") (pin "43") (pinfunction "43_43") (pintype "passive"))
    )
    (net (code "191") (name "Net-(P1-Pad29)") (class "Default")
      (node (ref "P1") (pin "29") (pinfunction "29_29") (pintype "passive"))
      (node (ref "T2") (pin "44") (pinfunction "44_44") (pintype "passive"))
    )
    (net (code "192") (name "Net-(P1-Pad30)") (class "Default")
      (node (ref "P1") (pin "30") (pinfunction "30_30") (pintype "passive"))
      (node (ref "T2") (pin "41") (pinfunction "41_41") (pintype "passive"))
    )
    (net (code "193") (name "Net-(P1-Pad31)") (class "Default")
      (node (ref "P1") (pin "31") (pinfunction "31_31") (pintype "passive"))
      (node (ref "T2") (pin "46") (pinfunction "46_46") (pintype "passive"))
    )
    (net (code "194") (name "Net-(P1-Pad32)") (class "Default")
      (node (ref "P1") (pin "32") (pinfunction "32_32") (pintype "passive"))
      (node (ref "T2") (pin "47") (pinfunction "47_47") (pintype "passive"))
    )
    (net (code "195") (name "Net-(R8-Pad2)") (class "Default")
      (node (ref "R8") (pin "2") (pinfunction "2_2") (pintype "passive"))
      (node (ref "U2") (pin "11") (pinfunction "SUSPEND_11") (pintype "passive"))
    )
    (net (code "196") (name "Net-(R19-Pad2)") (class "Default")
      (node (ref "R19") (pin "2") (pinfunction "2_2") (pintype "passive"))
      (node (ref "T1") (pin "27") (pinfunction "27_27") (pintype "passive"))
    )
    (net (code "197") (name "Net-(R20-Pad2)") (class "Default")
      (node (ref "R20") (pin "2") (pinfunction "2_2") (pintype "passive"))
      (node (ref "T1") (pin "30") (pinfunction "30_30") (pintype "passive"))
    )
    (net (code "198") (name "Net-(R21-Pad2)") (class "Default")
      (node (ref "R21") (pin "2") (pinfunction "2_2") (pintype "passive"))
      (node (ref "T1") (pin "33") (pinfunction "33_33") (pintype "passive"))
    )
    (net (code "199") (name "Net-(R22-Pad2)") (class "Default")
      (node (ref "R22") (pin "2") (pinfunction "2_2") (pintype "passive"))
      (node (ref "T1") (pin "36") (pinfunction "36_36") (pintype "passive"))
    )
    (net (code "200") (name "Net-(R23-Pad2)") (class "Default")
      (node (ref "R23") (pin "2") (pinfunction "2_2") (pintype "passive"))
      (node (ref "T1") (pin "39") (pinfunction "39_39") (pintype "passive"))
    )
    (net (code "201") (name "Net-(R24-Pad2)") (class "Default")
      (node (ref "R24") (pin "2") (pinfunction "2_2") (pintype "passive"))
      (node (ref "T1") (pin "42") (pinfunction "42_42") (pintype "passive"))
    )
    (net (code "202") (name "Net-(R25-Pad2)") (class "Default")
      (node (ref "R25") (pin "2") (pinfunction "2_2") (pintype "passive"))
      (node (ref "T1") (pin "45") (pinfunction "45_45") (pintype "passive"))
    )
    (net (code "203") (name "Net-(R26-Pad2)") (class "Default")
      (node (ref "R26") (pin "2") (pinfunction "2_2") (pintype "passive"))
      (node (ref "T1") (pin "48") (pinfunction "48_48") (pintype "passive"))
    )
    (net (code "204") (name "Net-(R27-Pad2)") (class "Default")
      (node (ref "R27") (pin "2") (pinfunction "2_2") (pintype "passive"))
      (node (ref "T2") (pin "27") (pinfunction "27_27") (pintype "passive"))
    )
    (net (code "205") (name "Net-(R28-Pad2)") (class "Default")
      (node (ref "R28") (pin "2") (pinfunction "2_2") (pintype "passive"))
      (node (ref "T2") (pin "30") (pinfunction "30_30") (pintype "passive"))
    )
    (net (code "206") (name "Net-(R29-Pad2)") (class "Default")
      (node (ref "R29") (pin "2") (pinfunction "2_2") (pintype "passive"))
      (node (ref "T2") (pin "33") (pinfunction "33_33") (pintype "passive"))
    )
    (net (code "207") (name "Net-(R30-Pad2)") (class "Default")
      (node (ref "R30") (pin "2") (pinfunction "2_2") (pintype "passive"))
      (node (ref "T2") (pin "36") (pinfunction "36_36") (pintype "passive"))
    )
    (net (code "208") (name "Net-(R31-Pad2)") (class "Default")
      (node (ref "R31") (pin "2") (pinfunction "2_2") (pintype "passive"))
      (node (ref "T2") (pin "39") (pinfunction "39_39") (pintype "passive"))
    )
    (net (code "209") (name "Net-(R32-Pad2)") (class "Default")
      (node (ref "R32") (pin "2") (pinfunction "2_2") (pintype "passive"))
      (node (ref "T2") (pin "42") (pinfunction "42_42") (pintype "passive"))
    )
    (net (code "210") (name "Net-(R33-Pad2)") (class "Default")
      (node (ref "R33") (pin "2") (pinfunction "2_2") (pintype "passive"))
      (node (ref "T2") (pin "45") (pinfunction "45_45") (pintype "passive"))
    )
    (net (code "211") (name "Net-(R34-Pad2)") (class "Default")
      (node (ref "R34") (pin "2") (pinfunction "2_2") (pintype "passive"))
      (node (ref "T2") (pin "48") (pinfunction "48_48") (pintype "passive"))
    )
    (net (code "212") (name "Net-(R35-Pad2)") (class "Default")
      (node (ref "R35") (pin "2") (pinfunction "2_2") (pintype "passive"))
      (node (ref "T3") (pin "15") (pinfunction "15_15") (pintype "passive"))
    )
    (net (code "213") (name "Net-(R36-Pad2)") (class "Default")
      (node (ref "R36") (pin "2") (pinfunction "2_2") (pintype "passive"))
      (node (ref "T3") (pin "18") (pinfunction "18_18") (pintype "passive"))
    )
    (net (code "214") (name "Net-(R37-Pad2)") (class "Default")
      (node (ref "R37") (pin "2") (pinfunction "2_2") (pintype "passive"))
      (node (ref "T3") (pin "21") (pinfunction "21_21") (pintype "passive"))
    )
    (net (code "215") (name "Net-(R38-Pad2)") (class "Default")
      (node (ref "R38") (pin "2") (pinfunction "2_2") (pintype "passive"))
      (node (ref "T3") (pin "24") (pinfunction "24_24") (pintype "passive"))
    )
    (net (code "216") (name "Net-(T3-Pad13)") (class "Default")
      (node (ref "T3") (pin "13") (pinfunction "13_13") (pintype "passive"))
      (node (ref "W1") (pin "1") (pinfunction "1_1") (pintype "passive"))
    )
    (net (code "217") (name "Net-(T3-Pad14)") (class "Default")
      (node (ref "T3") (pin "14") (pinfunction "14_14") (pintype "passive"))
      (node (ref "W1") (pin "2") (pinfunction "2_2") (pintype "passive"))
    )
    (net (code "218") (name "Net-(T3-Pad16)") (class "Default")
      (node (ref "T3") (pin "16") (pinfunction "16_16") (pintype "passive"))
      (node (ref "W1") (pin "3") (pinfunction "3_3") (pintype "passive"))
    )
    (net (code "219") (name "Net-(T3-Pad17)") (class "Default")
      (node (ref "T3") (pin "17") (pinfunction "17_17") (pintype "passive"))
      (node (ref "W1") (pin "6") (pinfunction "6_6") (pintype "passive"))
    )
    (net (code "220") (name "Net-(T3-Pad19)") (class "Default")
      (node (ref "T3") (pin "19") (pinfunction "19_19") (pintype "passive"))
      (node (ref "W1") (pin "4") (pinfunction "4_4") (pintype "passive"))
    )
    (net (code "221") (name "Net-(T3-Pad20)") (class "Default")
      (node (ref "T3") (pin "20") (pinfunction "20_20") (pintype "passive"))
      (node (ref "W1") (pin "5") (pinfunction "5_5") (pintype "passive"))
    )
    (net (code "222") (name "Net-(T3-Pad22)") (class "Default")
      (node (ref "T3") (pin "22") (pinfunction "22_22") (pintype "passive"))
      (node (ref "W1") (pin "7") (pinfunction "7_7") (pintype "passive"))
    )
    (net (code "223") (name "Net-(T3-Pad23)") (class "Default")
      (node (ref "T3") (pin "23") (pinfunction "23_23") (pintype "passive"))
      (node (ref "W1") (pin "8") (pinfunction "8_8") (pintype "passive"))
    )
    (net (code "224") (name "Net-(U1-BST)") (class "Default")
      (node (ref "C8") (pin "1") (pinfunction "1_1") (pintype "passive"))
      (node (ref "U1") (pin "8") (pinfunction "BST_8") (pintype "passive"))
    )
    (net (code "225") (name "Net-(U1-COMP)") (class "Default")
      (node (ref "C1") (pin "1") (pinfunction "1_1") (pintype "passive"))
      (node (ref "C2") (pin "1") (pinfunction "1_1") (pintype "passive"))
      (node (ref "U1") (pin "3") (pinfunction "COMP_3") (pintype "passive"))
    )
    (net (code "226") (name "Net-(U1-EN)") (class "Default")
      (node (ref "R5") (pin "2") (pinfunction "2_2") (pintype "passive"))
      (node (ref "R6") (pin "1") (pinfunction "1_1") (pintype "passive"))
      (node (ref "U1") (pin "2") (pinfunction "EN_2") (pintype "passive"))
    )
    (net (code "227") (name "Net-(U1-FB)") (class "Default")
      (node (ref "R1") (pin "2") (pinfunction "2_2") (pintype "passive"))
      (node (ref "R2") (pin "2") (pinfunction "2_2") (pintype "passive"))
      (node (ref "U1") (pin "4") (pinfunction "FB_4") (pintype "passive"))
    )
    (net (code "228") (name "Net-(U1-SW)") (class "Default")
      (node (ref "C8") (pin "2") (pinfunction "2_2") (pintype "passive"))
      (node (ref "L1") (pin "2") (pinfunction "2_2") (pintype "passive"))
      (node (ref "U1") (pin "1") (pinfunction "SW_1") (pintype "passive"))
      (node (ref "Z1") (pin "2") (pinfunction "K_2") (pintype "passive"))
    )
    (net (code "229") (name "Net-(U1-频率)") (class "Default")
      (node (ref "R3") (pin "2") (pinfunction "2_2") (pintype "passive"))
      (node (ref "U1") (pin "6") (pinfunction "频率_6") (pintype "passive"))
    )
    (net (code "230") (name "Net-(U2-RST)") (class "Default")
      (node (ref "R7") (pin "2") (pinfunction "2_2") (pintype "passive"))
      (node (ref "U2") (pin "9") (pinfunction "RST_9") (pintype "passive"))
    )
    (net (code "231") (name "Net-(U2-TXD)") (class "Default")
      (node (ref "R39") (pin "2") (pinfunction "2_2") (pintype "passive"))
      (node (ref "U2") (pin "26") (pinfunction "TXD_26") (pintype "passive"))
    )
    (net (code "232") (name "Net-(U2-VDD)") (class "Default")
      (node (ref "C3") (pin "2") (pinfunction "2_2") (pintype "passive"))
      (node (ref "R7") (pin "1") (pinfunction "1_1") (pintype "passive"))
      (node (ref "U2") (pin "6") (pinfunction "VDD_6") (pintype "passive"))
    )
    (net (code "233") (name "Net-(U3-BST)") (class "Default")
      (node (ref "C17") (pin "1") (pinfunction "1_1") (pintype "passive"))
      (node (ref "U3") (pin "8") (pinfunction "BST_8") (pintype "passive"))
    )
    (net (code "234") (name "Net-(U3-COMP)") (class "Default")
      (node (ref "C13") (pin "1") (pinfunction "1_1") (pintype "passive"))
      (node (ref "C14") (pin "1") (pinfunction "1_1") (pintype "passive"))
      (node (ref "U3") (pin "3") (pinfunction "COMP_3") (pintype "passive"))
    )
    (net (code "235") (name "Net-(U3-EN)") (class "Default")
      (node (ref "R13") (pin "2") (pinfunction "2_2") (pintype "passive"))
      (node (ref "R14") (pin "1") (pinfunction "1_1") (pintype "passive"))
      (node (ref "U3") (pin "2") (pinfunction "EN_2") (pintype "passive"))
    )
    (net (code "236") (name "Net-(U3-FB)") (class "Default")
      (node (ref "R10") (pin "2") (pinfunction "2_2") (pintype "passive"))
      (node (ref "R9") (pin "2") (pinfunction "2_2") (pintype "passive"))
      (node (ref "U3") (pin "4") (pinfunction "FB_4") (pintype "passive"))
    )
    (net (code "237") (name "Net-(U3-SW)") (class "Default")
      (node (ref "C17") (pin "2") (pinfunction "2_2") (pintype "passive"))
      (node (ref "L2") (pin "2") (pinfunction "2_2") (pintype "passive"))
      (node (ref "U3") (pin "1") (pinfunction "SW_1") (pintype "passive"))
      (node (ref "Z2") (pin "2") (pinfunction "K_2") (pintype "passive"))
    )
    (net (code "238") (name "Net-(U3-频率)") (class "Default")
      (node (ref "R11") (pin "2") (pinfunction "2_2") (pintype "passive"))
      (node (ref "U3") (pin "6") (pinfunction "频率_6") (pintype "passive"))
    )
    (net (code "239") (name "unconnected-(J1-0-Pad1)") (class "Default")
      (node (ref "J1") (pin "1") (pinfunction "0_1") (pintype "passive"))
    )
    (net (code "240") (name "unconnected-(J1-Pad3)") (class "Default")
      (node (ref "J1") (pin "3") (pinfunction "3_3") (pintype "passive"))
    )
    (net (code "241") (name "unconnected-(J1-Pad5)") (class "Default")
      (node (ref "J1") (pin "5") (pinfunction "5_5") (pintype "passive"))
    )
    (net (code "242") (name "unconnected-(J1-Pad6)") (class "Default")
      (node (ref "J1") (pin "6") (pinfunction "6_6") (pintype "passive"))
    )
    (net (code "243") (name "unconnected-(J1-Pad7)") (class "Default")
      (node (ref "J1") (pin "7") (pinfunction "7_7") (pintype "passive"))
    )
    (net (code "244") (name "unconnected-(J1-Pad8)") (class "Default")
      (node (ref "J1") (pin "8") (pinfunction "8_8") (pintype "passive"))
    )
    (net (code "245") (name "unconnected-(J1-Pad10)") (class "Default")
      (node (ref "J1") (pin "10") (pinfunction "10_10") (pintype "passive"))
    )
    (net (code "246") (name "unconnected-(J1-Pad12)") (class "Default")
      (node (ref "J1") (pin "12") (pinfunction "12_12") (pintype "passive"))
    )
    (net (code "247") (name "unconnected-(J1-Pad14)") (class "Default")
      (node (ref "J1") (pin "14") (pinfunction "14_14") (pintype "passive"))
    )
    (net (code "248") (name "unconnected-(J1-Pad16)") (class "Default")
      (node (ref "J1") (pin "16") (pinfunction "16_16") (pintype "passive"))
    )
    (net (code "249") (name "unconnected-(J1-Pad17)") (class "Default")
      (node (ref "J1") (pin "17") (pinfunction "17_17") (pintype "passive"))
    )
    (net (code "250") (name "unconnected-(J1-Pad19)") (class "Default")
      (node (ref "J1") (pin "19") (pinfunction "19_19") (pintype "passive"))
    )
    (net (code "251") (name "unconnected-(J1-Pad20)") (class "Default")
      (node (ref "J1") (pin "20") (pinfunction "20_20") (pintype "passive"))
    )
    (net (code "252") (name "unconnected-(J1-Pad28)") (class "Default")
      (node (ref "J1") (pin "28") (pinfunction "28_28") (pintype "passive"))
    )
    (net (code "253") (name "unconnected-(J1-Pad30)") (class "Default")
      (node (ref "J1") (pin "30") (pinfunction "30_30") (pintype "passive"))
    )
    (net (code "254") (name "unconnected-(J1-Pad32)") (class "Default")
      (node (ref "J1") (pin "32") (pinfunction "32_32") (pintype "passive"))
    )
    (net (code "255") (name "unconnected-(J1-Pad36)") (class "Default")
      (node (ref "J1") (pin "36") (pinfunction "36_36") (pintype "passive"))
    )
    (net (code "256") (name "unconnected-(J1-Pad38)") (class "Default")
      (node (ref "J1") (pin "38") (pinfunction "38_38") (pintype "passive"))
    )
    (net (code "257") (name "unconnected-(J1-Pad45)") (class "Default")
      (node (ref "J1") (pin "45") (pinfunction "45_45") (pintype "passive"))
    )
    (net (code "258") (name "unconnected-(J1-Pad51)") (class "Default")
      (node (ref "J1") (pin "51") (pinfunction "51_51") (pintype "passive"))
    )
    (net (code "259") (name "unconnected-(J1-Pad53)") (class "Default")
      (node (ref "J1") (pin "53") (pinfunction "53_53") (pintype "passive"))
    )
    (net (code "260") (name "unconnected-(J1-Pad54)") (class "Default")
      (node (ref "J1") (pin "54") (pinfunction "54_54") (pintype "passive"))
    )
    (net (code "261") (name "unconnected-(J1-Pad61)") (class "Default")
      (node (ref "J1") (pin "61") (pinfunction "61_61") (pintype "passive"))
    )
    (net (code "262") (name "unconnected-(J1-Pad62)") (class "Default")
      (node (ref "J1") (pin "62") (pinfunction "62_62") (pintype "passive"))
    )
    (net (code "263") (name "unconnected-(J1-Pad67)") (class "Default")
      (node (ref "J1") (pin "67") (pinfunction "67_67") (pintype "passive"))
    )
    (net (code "264") (name "unconnected-(J1-Pad68)") (class "Default")
      (node (ref "J1") (pin "68") (pinfunction "68_68") (pintype "passive"))
    )
    (net (code "265") (name "unconnected-(P1-Pad33)") (class "Default")
      (node (ref "P1") (pin "33") (pinfunction "33_33") (pintype "passive"))
    )
    (net (code "266") (name "unconnected-(P1-Pad34)") (class "Default")
      (node (ref "P1") (pin "34") (pinfunction "34_34") (pintype "passive"))
    )
    (net (code "267") (name "unconnected-(U2-CTS-Pad23)") (class "Default")
      (node (ref "U2") (pin "23") (pinfunction "CTS_23") (pintype "passive"))
    )
    (net (code "268") (name "unconnected-(U2-DCD-Pad1)") (class "Default")
      (node (ref "U2") (pin "1") (pinfunction "DCD_1") (pintype "passive"))
    )
    (net (code "269") (name "unconnected-(U2-DSR-Pad27)") (class "Default")
      (node (ref "U2") (pin "27") (pinfunction "DSR_27") (pintype "passive"))
    )
    (net (code "270") (name "unconnected-(U2-DTR-Pad28)") (class "Default")
      (node (ref "U2") (pin "28") (pinfunction "DTR_28") (pintype "passive"))
    )
    (net (code "271") (name "unconnected-(U2-NC1-Pad10)") (class "Default")
      (node (ref "U2") (pin "10") (pinfunction "NC1_10") (pintype "passive"))
    )
    (net (code "272") (name "unconnected-(U2-NC2-Pad13)") (class "Default")
      (node (ref "U2") (pin "13") (pinfunction "NC2_13") (pintype "passive"))
    )
    (net (code "273") (name "unconnected-(U2-NC3-Pad14)") (class "Default")
      (node (ref "U2") (pin "14") (pinfunction "NC3_14") (pintype "passive"))
    )
    (net (code "274") (name "unconnected-(U2-NC4-Pad15)") (class "Default")
      (node (ref "U2") (pin "15") (pinfunction "NC4_15") (pintype "passive"))
    )
    (net (code "275") (name "unconnected-(U2-NC5-Pad16)") (class "Default")
      (node (ref "U2") (pin "16") (pinfunction "NC5_16") (pintype "passive"))
    )
    (net (code "276") (name "unconnected-(U2-NC6-Pad17)") (class "Default")
      (node (ref "U2") (pin "17") (pinfunction "NC6_17") (pintype "passive"))
    )
    (net (code "277") (name "unconnected-(U2-NC7-Pad18)") (class "Default")
      (node (ref "U2") (pin "18") (pinfunction "NC7_18") (pintype "passive"))
    )
    (net (code "278") (name "unconnected-(U2-NC8-Pad19)") (class "Default")
      (node (ref "U2") (pin "19") (pinfunction "NC8_19") (pintype "passive"))
    )
    (net (code "279") (name "unconnected-(U2-NC9-Pad20)") (class "Default")
      (node (ref "U2") (pin "20") (pinfunction "NC9_20") (pintype "passive"))
    )
    (net (code "280") (name "unconnected-(U2-NC10-Pad21)") (class "Default")
      (node (ref "U2") (pin "21") (pinfunction "NC10_21") (pintype "passive"))
    )
    (net (code "281") (name "unconnected-(U2-NC11-Pad22)") (class "Default")
      (node (ref "U2") (pin "22") (pinfunction "NC11_22") (pintype "passive"))
    )
    (net (code "282") (name "unconnected-(U2-RI-Pad2)") (class "Default")
      (node (ref "U2") (pin "2") (pinfunction "RI_2") (pintype "passive"))
    )
    (net (code "283") (name "unconnected-(U2-RTS-Pad24)") (class "Default")
      (node (ref "U2") (pin "24") (pinfunction "RTS_24") (pintype "passive"))
    )
    (net (code "284") (name "unconnected-(U2-SUSPEND-Pad12)") (class "Default")
      (node (ref "U2") (pin "12") (pinfunction "SUSPEND_12") (pintype "passive"))
    )
    (net (code "285") (name "unconnected-(USB1-ID-Pad2)") (class "Default")
      (node (ref "USB1") (pin "2") (pinfunction "ID_2") (pintype "passive"))
    )
    (net (code "286") (name "unconnected-(W1-Pad9)") (class "Default")
      (node (ref "W1") (pin "9") (pinfunction "9_9") (pintype "passive"))
    )
  )
)
